# Urukul_FPGA_LVDS.net
KiCad netlist of a schematic drawn in Altium Designer
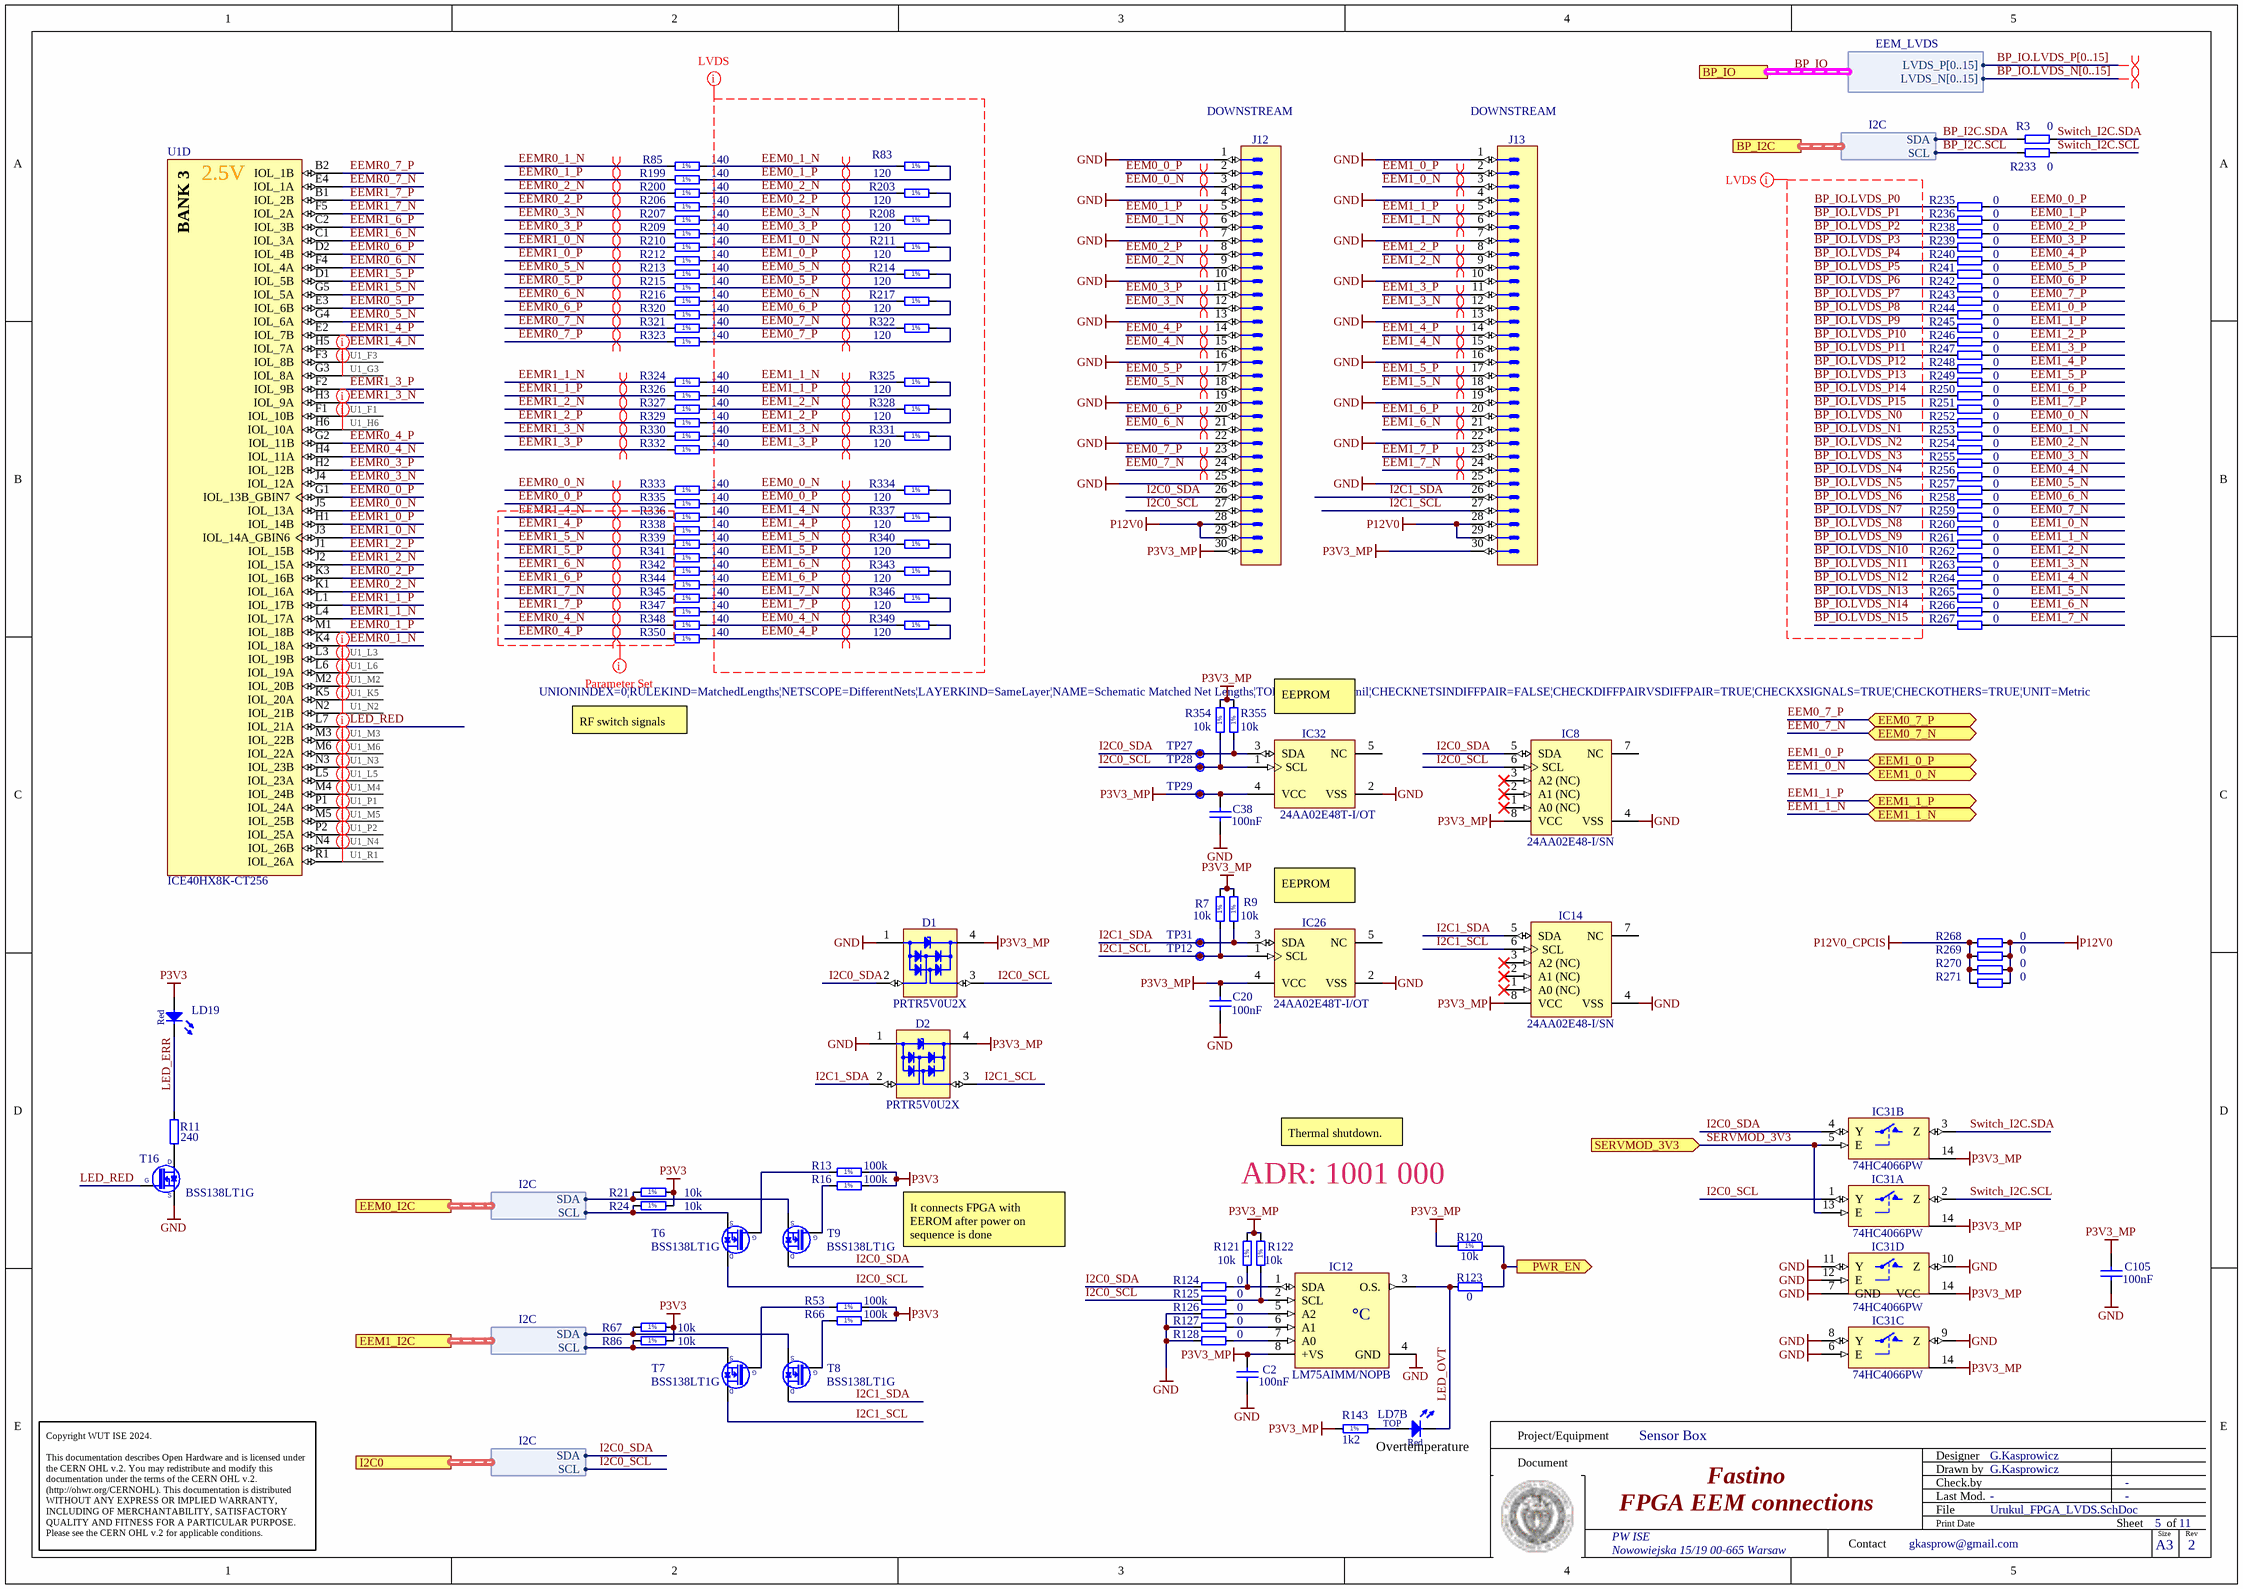
[diagram p0: Urukul_FPGA_LVDS.SchDoc]

(export (version "E")
  (design (tool "Eeschema 10.0.6"))
  (components
    (comp (ref "C2")
      (value "100nF")
      (footprint "CAPC1005X55N")
      (description "Non-polarised capacitor")
      (fields
        (field (name "PART NUMBER") "CC0402_100NF_16V_10%_X5R")
        (field (name "VOLTAGE") "16V")
        (field (name "AUTHOR") "CERN DEM JLC")
      )
      (libsource (lib "Capacitors") (part "Capacitor - non polarized"))
    )
    (comp (ref "C20")
      (value "100nF")
      (footprint "CAPC1005X55N")
      (description "Non-polarised capacitor")
      (fields
        (field (name "PART NUMBER") "CC0402_100NF_16V_10%_X5R")
        (field (name "VOLTAGE") "16V")
        (field (name "AUTHOR") "CERN DEM JLC")
      )
      (libsource (lib "Capacitors") (part "Capacitor - non polarized"))
    )
    (comp (ref "C38")
      (value "100nF")
      (footprint "CAPC1005X55N")
      (description "Non-polarised capacitor")
      (fields
        (field (name "PART NUMBER") "CC0402_100NF_16V_10%_X5R")
        (field (name "VOLTAGE") "16V")
        (field (name "AUTHOR") "CERN DEM JLC")
      )
      (libsource (lib "Capacitors") (part "Capacitor - non polarized"))
    )
    (comp (ref "C105")
      (value "100nF")
      (footprint "CAPC1005X55N")
      (description "Non-polarised capacitor")
      (fields
        (field (name "PART NUMBER") "CC0402_100NF_16V_10%_X5R")
        (field (name "VOLTAGE") "16V")
        (field (name "AUTHOR") "CERN DEM JLC")
      )
      (libsource (lib "Capacitors") (part "Capacitor - non polarized"))
    )
    (comp (ref "D1")
      (value "PRTR5V0U2X")
      (footprint "SOT190P230X110-4N")
      (description "Ultra Low Capacitance Double Rail-to-Rail ESD Protection Diode")
      (fields
        (field (name "VOLTAGE") "5.5V")
        (field (name "MANUFACTURER") "NXP SEMICONDUCTORS")
        (field (name "AUTHOR") "CERN DEM JLC")
      )
      (libsource (lib "ICs And Semiconductors") (part "PRTR5V0U2X"))
    )
    (comp (ref "D2")
      (value "PRTR5V0U2X")
      (footprint "SOT190P230X110-4N")
      (description "Ultra Low Capacitance Double Rail-to-Rail ESD Protection Diode")
      (fields
        (field (name "VOLTAGE") "5.5V")
        (field (name "MANUFACTURER") "NXP SEMICONDUCTORS")
        (field (name "AUTHOR") "CERN DEM JLC")
      )
      (libsource (lib "ICs And Semiconductors") (part "PRTR5V0U2X"))
    )
    (comp (ref "IC8")
      (value "24AA02E48-I/SN")
      (footprint "SOIC127P600X175-8N")
      (description "1.7V-5.5V, 2K I2C™ Serial EEPROMs with EUI-48™ Node Identity")
      (fields (field (name "MANUFACTURER") "MICROCHIP TECHNOLOGY") (field (name "AUTHOR") "CERN DEM MR"))
      (libsource (lib "ICS-logic") (part "MEM_24AA02E48-I/SN"))
    )
    (comp (ref "IC12")
      (value "LM75AIMM/NOPB")
      (footprint "SOP65P490X109-8N")
      (description "Digital Temperature Sensor and Thermal Watchdog with Two-Wire Interface")
      (fields (field (name "MANUFACTURER") "TEXAS INSTRUMENTS") (field (name "AUTHOR") "CERN DEM JLC"))
      (libsource (lib "ICs And Semiconductors") (part "LM75"))
    )
    (comp (ref "IC14")
      (value "24AA02E48-I/SN")
      (footprint "SOIC127P600X175-8N")
      (description "1.7V-5.5V, 2K I2C™ Serial EEPROMs with EUI-48™ Node Identity")
      (fields (field (name "MANUFACTURER") "MICROCHIP TECHNOLOGY") (field (name "AUTHOR") "CERN DEM MR"))
      (libsource (lib "ICS-logic") (part "MEM_24AA02E48-I/SN"))
    )
    (comp (ref "IC26")
      (value "24AA02E48T-I/OT")
      (footprint "SOT95P280X145-5N")
      (description "1.7V-5.5V, 2K I2C Serial EEPROM With EUI-48 Node Identity")
      (fields (field (name "MANUFACTURER") "MICROCHIP TECHNOLOGY") (field (name "AUTHOR") "CERN DEM MR"))
      (libsource (lib "ICs And Semiconductors") (part "24AA02E48T-I/OT"))
    )
    (comp (ref "IC31")
      (value "74HC4066PW")
      (footprint "SOP65P640X110-14N")
      (fields (field (name "MANUFACTURER") "NXP SEMICONDUCTORS") (field (name "AUTHOR") "CERN DEM JLC"))
      (libsource (lib "ICs And Semiconductors") (part "4066"))
    )
    (comp (ref "IC32")
      (value "24AA02E48T-I/OT")
      (footprint "SOT95P280X145-5N")
      (description "1.7V-5.5V, 2K I2C Serial EEPROM With EUI-48 Node Identity")
      (fields (field (name "MANUFACTURER") "MICROCHIP TECHNOLOGY") (field (name "AUTHOR") "CERN DEM MR"))
      (libsource (lib "ICs And Semiconductors") (part "24AA02E48T-I/OT"))
    )
    (comp (ref "J12")
      (value "~")
      (footprint "3M_N2530-6002RB")
      (description "Connector 30 Male")
      (fields
        (field (name "PART NUMBER") "3M_N2530-6002RB")
        (field (name "MANUFACTURER") "3M")
        (field (name "AUTHOR") "CERN DEM JLC")
      )
      (libsource (lib "Connectors") (part "Connector 30 Male"))
    )
    (comp (ref "J13")
      (value "~")
      (footprint "3M_N2530-6002RB")
      (description "Connector 30 Male")
      (fields
        (field (name "PART NUMBER") "3M_N2530-6002RB")
        (field (name "MANUFACTURER") "3M")
        (field (name "AUTHOR") "CERN DEM JLC")
      )
      (libsource (lib "Connectors") (part "Connector 30 Male"))
    )
    (comp (ref "LD7")
      (value "Red/Green")
      (footprint "LED_DIALIGHT_571-0112F")
      (description "2x LED  Botom Green, Top Red")
      (fields
        (field (name "PART NUMBER") "LED_DIALIGHT_571-0112F")
        (field (name "MANUFACTURER") "DIALIGHT")
        (field (name "AUTHOR") "CERN DEM JLC")
      )
      (libsource (lib "ICs And Semiconductors") (part "LED x2 G-1C2A-BOT_R-3C4A-TOP"))
    )
    (comp (ref "LD19")
      (value "Red")
      (footprint "LED_AVAGO_HSMC-C120")
      (description "LED Red 1C 2A")
      (fields
        (field (name "PART NUMBER") "LED_AVAGO_HSMC-C120")
        (field (name "MANUFACTURER") "AVAGO TECHNOLOGIES")
        (field (name "AUTHOR") "CERN DEM JMW")
      )
      (libsource (lib "ICs And Semiconductors") (part "LED Red 1C 2A"))
    )
    (comp (ref "R3")
      (value "0")
      (footprint "RESC1005X40N")
      (description "Resistor")
      (fields
        (field (name "PART NUMBER") "R0402_0R_JUMPER")
        (field (name "MANUFACTURER") "GENERIC")
        (field (name "AUTHOR") "CERN DEM JLC")
      )
      (libsource (lib "Resistors") (part "Resistor"))
    )
    (comp (ref "R7")
      (value "10k")
      (footprint "RESC1005X40N")
      (description "Resistor - 1%")
      (fields
        (field (name "PART NUMBER") "R0402_10K_1%_0.0625W_100PPM")
        (field (name "POWER") "0.0625W")
        (field (name "AUTHOR") "CERN DEM JLC")
      )
      (libsource (lib "Resistors") (part "Resistor - 1%"))
    )
    (comp (ref "R9")
      (value "10k")
      (footprint "RESC1005X40N")
      (description "Resistor - 1%")
      (fields
        (field (name "PART NUMBER") "R0402_10K_1%_0.0625W_100PPM")
        (field (name "POWER") "0.0625W")
        (field (name "AUTHOR") "CERN DEM JLC")
      )
      (libsource (lib "Resistors") (part "Resistor - 1%"))
    )
    (comp (ref "R11")
      (value "240")
      (footprint "RESC1005X40N")
      (description "Resistor - 1%")
      (fields
        (field (name "PART NUMBER") "R0402_240R_1%_0.0625W_100PPM")
        (field (name "POWER") "0.0625W")
        (field (name "AUTHOR") "CERN DEM JLC")
      )
      (libsource (lib "Resistors") (part "Resistor - 1%"))
    )
    (comp (ref "R13")
      (value "100k")
      (footprint "RESC1005X40N")
      (description "Resistor - 1%")
      (fields
        (field (name "PART NUMBER") "R0402_100K_1%_0.0625W_100PPM")
        (field (name "POWER") "0.0625W")
        (field (name "AUTHOR") "CERN DEM JLC")
      )
      (libsource (lib "Resistors") (part "Resistor - 1%"))
    )
    (comp (ref "R16")
      (value "100k")
      (footprint "RESC1005X40N")
      (description "Resistor - 1%")
      (fields
        (field (name "PART NUMBER") "R0402_100K_1%_0.0625W_100PPM")
        (field (name "POWER") "0.0625W")
        (field (name "AUTHOR") "CERN DEM JLC")
      )
      (libsource (lib "Resistors") (part "Resistor - 1%"))
    )
    (comp (ref "R21")
      (value "10k")
      (footprint "RESC1005X40N")
      (description "Resistor - 1%")
      (fields
        (field (name "PART NUMBER") "R0402_10K_1%_0.0625W_100PPM")
        (field (name "POWER") "0.0625W")
        (field (name "AUTHOR") "CERN DEM JLC")
      )
      (libsource (lib "Resistors") (part "Resistor - 1%"))
    )
    (comp (ref "R24")
      (value "10k")
      (footprint "RESC1005X40N")
      (description "Resistor - 1%")
      (fields
        (field (name "PART NUMBER") "R0402_10K_1%_0.0625W_100PPM")
        (field (name "POWER") "0.0625W")
        (field (name "AUTHOR") "CERN DEM JLC")
      )
      (libsource (lib "Resistors") (part "Resistor - 1%"))
    )
    (comp (ref "R53")
      (value "100k")
      (footprint "RESC1005X40N")
      (description "Resistor - 1%")
      (fields
        (field (name "PART NUMBER") "R0402_100K_1%_0.0625W_100PPM")
        (field (name "POWER") "0.0625W")
        (field (name "AUTHOR") "CERN DEM JLC")
      )
      (libsource (lib "Resistors") (part "Resistor - 1%"))
    )
    (comp (ref "R66")
      (value "100k")
      (footprint "RESC1005X40N")
      (description "Resistor - 1%")
      (fields
        (field (name "PART NUMBER") "R0402_100K_1%_0.0625W_100PPM")
        (field (name "POWER") "0.0625W")
        (field (name "AUTHOR") "CERN DEM JLC")
      )
      (libsource (lib "Resistors") (part "Resistor - 1%"))
    )
    (comp (ref "R67")
      (value "10k")
      (footprint "RESC1005X40N")
      (description "Resistor - 1%")
      (fields
        (field (name "PART NUMBER") "R0402_10K_1%_0.0625W_100PPM")
        (field (name "POWER") "0.0625W")
        (field (name "AUTHOR") "CERN DEM JLC")
      )
      (libsource (lib "Resistors") (part "Resistor - 1%"))
    )
    (comp (ref "R83")
      (value "120")
      (footprint "RESC1005X40N")
      (description "Resistor - 1%")
      (fields
        (field (name "PART NUMBER") "R0402_120R_1%_0.0625W_100PPM")
        (field (name "POWER") "0.0625W")
        (field (name "AUTHOR") "CERN DEM JLC")
      )
      (libsource (lib "Resistors") (part "Resistor - 1%"))
    )
    (comp (ref "R85")
      (value "140")
      (footprint "RESC0603X28N")
      (description "Resistor - 1%")
      (fields
        (field (name "PART NUMBER") "R0201_140R_1%_0.05W_200PPM")
        (field (name "POWER") "0.05W")
        (field (name "AUTHOR") "CERN DEM MR")
      )
      (libsource (lib "Resistors") (part "Resistor - 1%"))
    )
    (comp (ref "R86")
      (value "10k")
      (footprint "RESC1005X40N")
      (description "Resistor - 1%")
      (fields
        (field (name "PART NUMBER") "R0402_10K_1%_0.0625W_100PPM")
        (field (name "POWER") "0.0625W")
        (field (name "AUTHOR") "CERN DEM JLC")
      )
      (libsource (lib "Resistors") (part "Resistor - 1%"))
    )
    (comp (ref "R120")
      (value "10k")
      (footprint "RESC1005X40N")
      (description "Resistor - 1%")
      (fields
        (field (name "PART NUMBER") "R0402_10K_1%_0.0625W_100PPM")
        (field (name "POWER") "0.0625W")
        (field (name "AUTHOR") "CERN DEM JLC")
      )
      (libsource (lib "Resistors") (part "Resistor - 1%"))
    )
    (comp (ref "R121")
      (value "10k")
      (footprint "RESC1005X40N")
      (description "Resistor - 1%")
      (fields
        (field (name "PART NUMBER") "R0402_10K_1%_0.0625W_100PPM")
        (field (name "POWER") "0.0625W")
        (field (name "AUTHOR") "CERN DEM JLC")
      )
      (libsource (lib "Resistors") (part "Resistor - 1%"))
    )
    (comp (ref "R122")
      (value "10k")
      (footprint "RESC1005X40N")
      (description "Resistor - 1%")
      (fields
        (field (name "PART NUMBER") "R0402_10K_1%_0.0625W_100PPM")
        (field (name "POWER") "0.0625W")
        (field (name "AUTHOR") "CERN DEM JLC")
      )
      (libsource (lib "Resistors") (part "Resistor - 1%"))
    )
    (comp (ref "R123")
      (value "0")
      (footprint "RESC1005X40N")
      (description "Resistor")
      (fields
        (field (name "PART NUMBER") "R0402_0R_JUMPER")
        (field (name "MANUFACTURER") "GENERIC")
        (field (name "AUTHOR") "CERN DEM JLC")
      )
      (libsource (lib "Resistors") (part "Resistor"))
    )
    (comp (ref "R124")
      (value "0")
      (footprint "RESC1005X40N")
      (description "Resistor")
      (fields
        (field (name "PART NUMBER") "R0402_0R_JUMPER")
        (field (name "MANUFACTURER") "GENERIC")
        (field (name "AUTHOR") "CERN DEM JLC")
      )
      (libsource (lib "Resistors") (part "Resistor"))
    )
    (comp (ref "R125")
      (value "0")
      (footprint "RESC1005X40N")
      (description "Resistor")
      (fields
        (field (name "PART NUMBER") "R0402_0R_JUMPER")
        (field (name "MANUFACTURER") "GENERIC")
        (field (name "AUTHOR") "CERN DEM JLC")
      )
      (libsource (lib "Resistors") (part "Resistor"))
    )
    (comp (ref "R126")
      (value "0")
      (footprint "RESC1005X40N")
      (description "Resistor")
      (fields
        (field (name "PART NUMBER") "R0402_0R_JUMPER")
        (field (name "MANUFACTURER") "GENERIC")
        (field (name "AUTHOR") "CERN DEM JLC")
      )
      (libsource (lib "Resistors") (part "Resistor"))
    )
    (comp (ref "R127")
      (value "0")
      (footprint "RESC1005X40N")
      (description "Resistor")
      (fields
        (field (name "PART NUMBER") "R0402_0R_JUMPER")
        (field (name "MANUFACTURER") "GENERIC")
        (field (name "AUTHOR") "CERN DEM JLC")
      )
      (libsource (lib "Resistors") (part "Resistor"))
    )
    (comp (ref "R128")
      (value "0")
      (footprint "RESC1005X40N")
      (description "Resistor")
      (fields
        (field (name "PART NUMBER") "R0402_0R_JUMPER")
        (field (name "MANUFACTURER") "GENERIC")
        (field (name "AUTHOR") "CERN DEM JLC")
      )
      (libsource (lib "Resistors") (part "Resistor"))
    )
    (comp (ref "R143")
      (value "1k2")
      (footprint "RESC1608X55N")
      (description "Resistor - 1%")
      (fields
        (field (name "PART NUMBER") "R0603_1K2_1%_0.1W_100PPM")
        (field (name "POWER") "0.1W")
        (field (name "AUTHOR") "CERN DEM JLC")
      )
      (libsource (lib "Resistors") (part "Resistor - 1%"))
    )
    (comp (ref "R199")
      (value "140")
      (footprint "RESC0603X28N")
      (description "Resistor - 1%")
      (fields
        (field (name "PART NUMBER") "R0201_140R_1%_0.05W_200PPM")
        (field (name "POWER") "0.05W")
        (field (name "AUTHOR") "CERN DEM MR")
      )
      (libsource (lib "Resistors") (part "Resistor - 1%"))
    )
    (comp (ref "R200")
      (value "140")
      (footprint "RESC0603X28N")
      (description "Resistor - 1%")
      (fields
        (field (name "PART NUMBER") "R0201_140R_1%_0.05W_200PPM")
        (field (name "POWER") "0.05W")
        (field (name "AUTHOR") "CERN DEM MR")
      )
      (libsource (lib "Resistors") (part "Resistor - 1%"))
    )
    (comp (ref "R203")
      (value "120")
      (footprint "RESC1005X40N")
      (description "Resistor - 1%")
      (fields
        (field (name "PART NUMBER") "R0402_120R_1%_0.0625W_100PPM")
        (field (name "POWER") "0.0625W")
        (field (name "AUTHOR") "CERN DEM JLC")
      )
      (libsource (lib "Resistors") (part "Resistor - 1%"))
    )
    (comp (ref "R206")
      (value "140")
      (footprint "RESC0603X28N")
      (description "Resistor - 1%")
      (fields
        (field (name "PART NUMBER") "R0201_140R_1%_0.05W_200PPM")
        (field (name "POWER") "0.05W")
        (field (name "AUTHOR") "CERN DEM MR")
      )
      (libsource (lib "Resistors") (part "Resistor - 1%"))
    )
    (comp (ref "R207")
      (value "140")
      (footprint "RESC0603X28N")
      (description "Resistor - 1%")
      (fields
        (field (name "PART NUMBER") "R0201_140R_1%_0.05W_200PPM")
        (field (name "POWER") "0.05W")
        (field (name "AUTHOR") "CERN DEM MR")
      )
      (libsource (lib "Resistors") (part "Resistor - 1%"))
    )
    (comp (ref "R208")
      (value "120")
      (footprint "RESC1005X40N")
      (description "Resistor - 1%")
      (fields
        (field (name "PART NUMBER") "R0402_120R_1%_0.0625W_100PPM")
        (field (name "POWER") "0.0625W")
        (field (name "AUTHOR") "CERN DEM JLC")
      )
      (libsource (lib "Resistors") (part "Resistor - 1%"))
    )
    (comp (ref "R209")
      (value "140")
      (footprint "RESC0603X28N")
      (description "Resistor - 1%")
      (fields
        (field (name "PART NUMBER") "R0201_140R_1%_0.05W_200PPM")
        (field (name "POWER") "0.05W")
        (field (name "AUTHOR") "CERN DEM MR")
      )
      (libsource (lib "Resistors") (part "Resistor - 1%"))
    )
    (comp (ref "R210")
      (value "140")
      (footprint "RESC0603X28N")
      (description "Resistor - 1%")
      (fields
        (field (name "PART NUMBER") "R0201_140R_1%_0.05W_200PPM")
        (field (name "POWER") "0.05W")
        (field (name "AUTHOR") "CERN DEM MR")
      )
      (libsource (lib "Resistors") (part "Resistor - 1%"))
    )
    (comp (ref "R211")
      (value "120")
      (footprint "RESC1005X40N")
      (description "Resistor - 1%")
      (fields
        (field (name "PART NUMBER") "R0402_120R_1%_0.0625W_100PPM")
        (field (name "POWER") "0.0625W")
        (field (name "AUTHOR") "CERN DEM JLC")
      )
      (libsource (lib "Resistors") (part "Resistor - 1%"))
    )
    (comp (ref "R212")
      (value "140")
      (footprint "RESC0603X28N")
      (description "Resistor - 1%")
      (fields
        (field (name "PART NUMBER") "R0201_140R_1%_0.05W_200PPM")
        (field (name "POWER") "0.05W")
        (field (name "AUTHOR") "CERN DEM MR")
      )
      (libsource (lib "Resistors") (part "Resistor - 1%"))
    )
    (comp (ref "R213")
      (value "140")
      (footprint "RESC0603X28N")
      (description "Resistor - 1%")
      (fields
        (field (name "PART NUMBER") "R0201_140R_1%_0.05W_200PPM")
        (field (name "POWER") "0.05W")
        (field (name "AUTHOR") "CERN DEM MR")
      )
      (libsource (lib "Resistors") (part "Resistor - 1%"))
    )
    (comp (ref "R214")
      (value "120")
      (footprint "RESC1005X40N")
      (description "Resistor - 1%")
      (fields
        (field (name "PART NUMBER") "R0402_120R_1%_0.0625W_100PPM")
        (field (name "POWER") "0.0625W")
        (field (name "AUTHOR") "CERN DEM JLC")
      )
      (libsource (lib "Resistors") (part "Resistor - 1%"))
    )
    (comp (ref "R215")
      (value "140")
      (footprint "RESC0603X28N")
      (description "Resistor - 1%")
      (fields
        (field (name "PART NUMBER") "R0201_140R_1%_0.05W_200PPM")
        (field (name "POWER") "0.05W")
        (field (name "AUTHOR") "CERN DEM MR")
      )
      (libsource (lib "Resistors") (part "Resistor - 1%"))
    )
    (comp (ref "R216")
      (value "140")
      (footprint "RESC0603X28N")
      (description "Resistor - 1%")
      (fields
        (field (name "PART NUMBER") "R0201_140R_1%_0.05W_200PPM")
        (field (name "POWER") "0.05W")
        (field (name "AUTHOR") "CERN DEM MR")
      )
      (libsource (lib "Resistors") (part "Resistor - 1%"))
    )
    (comp (ref "R217")
      (value "120")
      (footprint "RESC1005X40N")
      (description "Resistor - 1%")
      (fields
        (field (name "PART NUMBER") "R0402_120R_1%_0.0625W_100PPM")
        (field (name "POWER") "0.0625W")
        (field (name "AUTHOR") "CERN DEM JLC")
      )
      (libsource (lib "Resistors") (part "Resistor - 1%"))
    )
    (comp (ref "R233")
      (value "0")
      (footprint "RESC1005X40N")
      (description "Resistor")
      (fields
        (field (name "PART NUMBER") "R0402_0R_JUMPER")
        (field (name "MANUFACTURER") "GENERIC")
        (field (name "AUTHOR") "CERN DEM JLC")
      )
      (libsource (lib "Resistors") (part "Resistor"))
    )
    (comp (ref "R235")
      (value "0")
      (footprint "RESC1005X40N")
      (description "Resistor")
      (fields
        (field (name "PART NUMBER") "R0402_0R_JUMPER")
        (field (name "MANUFACTURER") "GENERIC")
        (field (name "AUTHOR") "CERN DEM JLC")
      )
      (libsource (lib "Resistors") (part "Resistor"))
    )
    (comp (ref "R236")
      (value "0")
      (footprint "RESC1005X40N")
      (description "Resistor")
      (fields
        (field (name "PART NUMBER") "R0402_0R_JUMPER")
        (field (name "MANUFACTURER") "GENERIC")
        (field (name "AUTHOR") "CERN DEM JLC")
      )
      (libsource (lib "Resistors") (part "Resistor"))
    )
    (comp (ref "R238")
      (value "0")
      (footprint "RESC1005X40N")
      (description "Resistor")
      (fields
        (field (name "PART NUMBER") "R0402_0R_JUMPER")
        (field (name "MANUFACTURER") "GENERIC")
        (field (name "AUTHOR") "CERN DEM JLC")
      )
      (libsource (lib "Resistors") (part "Resistor"))
    )
    (comp (ref "R239")
      (value "0")
      (footprint "RESC1005X40N")
      (description "Resistor")
      (fields
        (field (name "PART NUMBER") "R0402_0R_JUMPER")
        (field (name "MANUFACTURER") "GENERIC")
        (field (name "AUTHOR") "CERN DEM JLC")
      )
      (libsource (lib "Resistors") (part "Resistor"))
    )
    (comp (ref "R240")
      (value "0")
      (footprint "RESC1005X40N")
      (description "Resistor")
      (fields
        (field (name "PART NUMBER") "R0402_0R_JUMPER")
        (field (name "MANUFACTURER") "GENERIC")
        (field (name "AUTHOR") "CERN DEM JLC")
      )
      (libsource (lib "Resistors") (part "Resistor"))
    )
    (comp (ref "R241")
      (value "0")
      (footprint "RESC1005X40N")
      (description "Resistor")
      (fields
        (field (name "PART NUMBER") "R0402_0R_JUMPER")
        (field (name "MANUFACTURER") "GENERIC")
        (field (name "AUTHOR") "CERN DEM JLC")
      )
      (libsource (lib "Resistors") (part "Resistor"))
    )
    (comp (ref "R242")
      (value "0")
      (footprint "RESC1005X40N")
      (description "Resistor")
      (fields
        (field (name "PART NUMBER") "R0402_0R_JUMPER")
        (field (name "MANUFACTURER") "GENERIC")
        (field (name "AUTHOR") "CERN DEM JLC")
      )
      (libsource (lib "Resistors") (part "Resistor"))
    )
    (comp (ref "R243")
      (value "0")
      (footprint "RESC1005X40N")
      (description "Resistor")
      (fields
        (field (name "PART NUMBER") "R0402_0R_JUMPER")
        (field (name "MANUFACTURER") "GENERIC")
        (field (name "AUTHOR") "CERN DEM JLC")
      )
      (libsource (lib "Resistors") (part "Resistor"))
    )
    (comp (ref "R244")
      (value "0")
      (footprint "RESC1005X40N")
      (description "Resistor")
      (fields
        (field (name "PART NUMBER") "R0402_0R_JUMPER")
        (field (name "MANUFACTURER") "GENERIC")
        (field (name "AUTHOR") "CERN DEM JLC")
      )
      (libsource (lib "Resistors") (part "Resistor"))
    )
    (comp (ref "R245")
      (value "0")
      (footprint "RESC1005X40N")
      (description "Resistor")
      (fields
        (field (name "PART NUMBER") "R0402_0R_JUMPER")
        (field (name "MANUFACTURER") "GENERIC")
        (field (name "AUTHOR") "CERN DEM JLC")
      )
      (libsource (lib "Resistors") (part "Resistor"))
    )
    (comp (ref "R246")
      (value "0")
      (footprint "RESC1005X40N")
      (description "Resistor")
      (fields
        (field (name "PART NUMBER") "R0402_0R_JUMPER")
        (field (name "MANUFACTURER") "GENERIC")
        (field (name "AUTHOR") "CERN DEM JLC")
      )
      (libsource (lib "Resistors") (part "Resistor"))
    )
    (comp (ref "R247")
      (value "0")
      (footprint "RESC1005X40N")
      (description "Resistor")
      (fields
        (field (name "PART NUMBER") "R0402_0R_JUMPER")
        (field (name "MANUFACTURER") "GENERIC")
        (field (name "AUTHOR") "CERN DEM JLC")
      )
      (libsource (lib "Resistors") (part "Resistor"))
    )
    (comp (ref "R248")
      (value "0")
      (footprint "RESC1005X40N")
      (description "Resistor")
      (fields
        (field (name "PART NUMBER") "R0402_0R_JUMPER")
        (field (name "MANUFACTURER") "GENERIC")
        (field (name "AUTHOR") "CERN DEM JLC")
      )
      (libsource (lib "Resistors") (part "Resistor"))
    )
    (comp (ref "R249")
      (value "0")
      (footprint "RESC1005X40N")
      (description "Resistor")
      (fields
        (field (name "PART NUMBER") "R0402_0R_JUMPER")
        (field (name "MANUFACTURER") "GENERIC")
        (field (name "AUTHOR") "CERN DEM JLC")
      )
      (libsource (lib "Resistors") (part "Resistor"))
    )
    (comp (ref "R250")
      (value "0")
      (footprint "RESC1005X40N")
      (description "Resistor")
      (fields
        (field (name "PART NUMBER") "R0402_0R_JUMPER")
        (field (name "MANUFACTURER") "GENERIC")
        (field (name "AUTHOR") "CERN DEM JLC")
      )
      (libsource (lib "Resistors") (part "Resistor"))
    )
    (comp (ref "R251")
      (value "0")
      (footprint "RESC1005X40N")
      (description "Resistor")
      (fields
        (field (name "PART NUMBER") "R0402_0R_JUMPER")
        (field (name "MANUFACTURER") "GENERIC")
        (field (name "AUTHOR") "CERN DEM JLC")
      )
      (libsource (lib "Resistors") (part "Resistor"))
    )
    (comp (ref "R252")
      (value "0")
      (footprint "RESC1005X40N")
      (description "Resistor")
      (fields
        (field (name "PART NUMBER") "R0402_0R_JUMPER")
        (field (name "MANUFACTURER") "GENERIC")
        (field (name "AUTHOR") "CERN DEM JLC")
      )
      (libsource (lib "Resistors") (part "Resistor"))
    )
    (comp (ref "R253")
      (value "0")
      (footprint "RESC1005X40N")
      (description "Resistor")
      (fields
        (field (name "PART NUMBER") "R0402_0R_JUMPER")
        (field (name "MANUFACTURER") "GENERIC")
        (field (name "AUTHOR") "CERN DEM JLC")
      )
      (libsource (lib "Resistors") (part "Resistor"))
    )
    (comp (ref "R254")
      (value "0")
      (footprint "RESC1005X40N")
      (description "Resistor")
      (fields
        (field (name "PART NUMBER") "R0402_0R_JUMPER")
        (field (name "MANUFACTURER") "GENERIC")
        (field (name "AUTHOR") "CERN DEM JLC")
      )
      (libsource (lib "Resistors") (part "Resistor"))
    )
    (comp (ref "R255")
      (value "0")
      (footprint "RESC1005X40N")
      (description "Resistor")
      (fields
        (field (name "PART NUMBER") "R0402_0R_JUMPER")
        (field (name "MANUFACTURER") "GENERIC")
        (field (name "AUTHOR") "CERN DEM JLC")
      )
      (libsource (lib "Resistors") (part "Resistor"))
    )
    (comp (ref "R256")
      (value "0")
      (footprint "RESC1005X40N")
      (description "Resistor")
      (fields
        (field (name "PART NUMBER") "R0402_0R_JUMPER")
        (field (name "MANUFACTURER") "GENERIC")
        (field (name "AUTHOR") "CERN DEM JLC")
      )
      (libsource (lib "Resistors") (part "Resistor"))
    )
    (comp (ref "R257")
      (value "0")
      (footprint "RESC1005X40N")
      (description "Resistor")
      (fields
        (field (name "PART NUMBER") "R0402_0R_JUMPER")
        (field (name "MANUFACTURER") "GENERIC")
        (field (name "AUTHOR") "CERN DEM JLC")
      )
      (libsource (lib "Resistors") (part "Resistor"))
    )
    (comp (ref "R258")
      (value "0")
      (footprint "RESC1005X40N")
      (description "Resistor")
      (fields
        (field (name "PART NUMBER") "R0402_0R_JUMPER")
        (field (name "MANUFACTURER") "GENERIC")
        (field (name "AUTHOR") "CERN DEM JLC")
      )
      (libsource (lib "Resistors") (part "Resistor"))
    )
    (comp (ref "R259")
      (value "0")
      (footprint "RESC1005X40N")
      (description "Resistor")
      (fields
        (field (name "PART NUMBER") "R0402_0R_JUMPER")
        (field (name "MANUFACTURER") "GENERIC")
        (field (name "AUTHOR") "CERN DEM JLC")
      )
      (libsource (lib "Resistors") (part "Resistor"))
    )
    (comp (ref "R260")
      (value "0")
      (footprint "RESC1005X40N")
      (description "Resistor")
      (fields
        (field (name "PART NUMBER") "R0402_0R_JUMPER")
        (field (name "MANUFACTURER") "GENERIC")
        (field (name "AUTHOR") "CERN DEM JLC")
      )
      (libsource (lib "Resistors") (part "Resistor"))
    )
    (comp (ref "R261")
      (value "0")
      (footprint "RESC1005X40N")
      (description "Resistor")
      (fields
        (field (name "PART NUMBER") "R0402_0R_JUMPER")
        (field (name "MANUFACTURER") "GENERIC")
        (field (name "AUTHOR") "CERN DEM JLC")
      )
      (libsource (lib "Resistors") (part "Resistor"))
    )
    (comp (ref "R262")
      (value "0")
      (footprint "RESC1005X40N")
      (description "Resistor")
      (fields
        (field (name "PART NUMBER") "R0402_0R_JUMPER")
        (field (name "MANUFACTURER") "GENERIC")
        (field (name "AUTHOR") "CERN DEM JLC")
      )
      (libsource (lib "Resistors") (part "Resistor"))
    )
    (comp (ref "R263")
      (value "0")
      (footprint "RESC1005X40N")
      (description "Resistor")
      (fields
        (field (name "PART NUMBER") "R0402_0R_JUMPER")
        (field (name "MANUFACTURER") "GENERIC")
        (field (name "AUTHOR") "CERN DEM JLC")
      )
      (libsource (lib "Resistors") (part "Resistor"))
    )
    (comp (ref "R264")
      (value "0")
      (footprint "RESC1005X40N")
      (description "Resistor")
      (fields
        (field (name "PART NUMBER") "R0402_0R_JUMPER")
        (field (name "MANUFACTURER") "GENERIC")
        (field (name "AUTHOR") "CERN DEM JLC")
      )
      (libsource (lib "Resistors") (part "Resistor"))
    )
    (comp (ref "R265")
      (value "0")
      (footprint "RESC1005X40N")
      (description "Resistor")
      (fields
        (field (name "PART NUMBER") "R0402_0R_JUMPER")
        (field (name "MANUFACTURER") "GENERIC")
        (field (name "AUTHOR") "CERN DEM JLC")
      )
      (libsource (lib "Resistors") (part "Resistor"))
    )
    (comp (ref "R266")
      (value "0")
      (footprint "RESC1005X40N")
      (description "Resistor")
      (fields
        (field (name "PART NUMBER") "R0402_0R_JUMPER")
        (field (name "MANUFACTURER") "GENERIC")
        (field (name "AUTHOR") "CERN DEM JLC")
      )
      (libsource (lib "Resistors") (part "Resistor"))
    )
    (comp (ref "R267")
      (value "0")
      (footprint "RESC1005X40N")
      (description "Resistor")
      (fields
        (field (name "PART NUMBER") "R0402_0R_JUMPER")
        (field (name "MANUFACTURER") "GENERIC")
        (field (name "AUTHOR") "CERN DEM JLC")
      )
      (libsource (lib "Resistors") (part "Resistor"))
    )
    (comp (ref "R268")
      (value "0")
      (footprint "RESC1005X40N")
      (description "Resistor")
      (fields
        (field (name "PART NUMBER") "R0402_0R_JUMPER")
        (field (name "MANUFACTURER") "GENERIC")
        (field (name "AUTHOR") "CERN DEM JLC")
      )
      (libsource (lib "Resistors") (part "Resistor"))
    )
    (comp (ref "R269")
      (value "0")
      (footprint "RESC1005X40N")
      (description "Resistor")
      (fields
        (field (name "PART NUMBER") "R0402_0R_JUMPER")
        (field (name "MANUFACTURER") "GENERIC")
        (field (name "AUTHOR") "CERN DEM JLC")
      )
      (libsource (lib "Resistors") (part "Resistor"))
    )
    (comp (ref "R270")
      (value "0")
      (footprint "RESC1005X40N")
      (description "Resistor")
      (fields
        (field (name "PART NUMBER") "R0402_0R_JUMPER")
        (field (name "MANUFACTURER") "GENERIC")
        (field (name "AUTHOR") "CERN DEM JLC")
      )
      (libsource (lib "Resistors") (part "Resistor"))
    )
    (comp (ref "R271")
      (value "0")
      (footprint "RESC1005X40N")
      (description "Resistor")
      (fields
        (field (name "PART NUMBER") "R0402_0R_JUMPER")
        (field (name "MANUFACTURER") "GENERIC")
        (field (name "AUTHOR") "CERN DEM JLC")
      )
      (libsource (lib "Resistors") (part "Resistor"))
    )
    (comp (ref "R320")
      (value "140")
      (footprint "RESC0603X28N")
      (description "Resistor - 1%")
      (fields
        (field (name "PART NUMBER") "R0201_140R_1%_0.05W_200PPM")
        (field (name "POWER") "0.05W")
        (field (name "AUTHOR") "CERN DEM MR")
      )
      (libsource (lib "Resistors") (part "Resistor - 1%"))
    )
    (comp (ref "R321")
      (value "140")
      (footprint "RESC0603X28N")
      (description "Resistor - 1%")
      (fields
        (field (name "PART NUMBER") "R0201_140R_1%_0.05W_200PPM")
        (field (name "POWER") "0.05W")
        (field (name "AUTHOR") "CERN DEM MR")
      )
      (libsource (lib "Resistors") (part "Resistor - 1%"))
    )
    (comp (ref "R322")
      (value "120")
      (footprint "RESC1005X40N")
      (description "Resistor - 1%")
      (fields
        (field (name "PART NUMBER") "R0402_120R_1%_0.0625W_100PPM")
        (field (name "POWER") "0.0625W")
        (field (name "AUTHOR") "CERN DEM JLC")
      )
      (libsource (lib "Resistors") (part "Resistor - 1%"))
    )
    (comp (ref "R323")
      (value "140")
      (footprint "RESC0603X28N")
      (description "Resistor - 1%")
      (fields
        (field (name "PART NUMBER") "R0201_140R_1%_0.05W_200PPM")
        (field (name "POWER") "0.05W")
        (field (name "AUTHOR") "CERN DEM MR")
      )
      (libsource (lib "Resistors") (part "Resistor - 1%"))
    )
    (comp (ref "R324")
      (value "140")
      (footprint "RESC0603X28N")
      (description "Resistor - 1%")
      (fields
        (field (name "PART NUMBER") "R0201_140R_1%_0.05W_200PPM")
        (field (name "POWER") "0.05W")
        (field (name "AUTHOR") "CERN DEM MR")
      )
      (libsource (lib "Resistors") (part "Resistor - 1%"))
    )
    (comp (ref "R325")
      (value "120")
      (footprint "RESC1005X40N")
      (description "Resistor - 1%")
      (fields
        (field (name "PART NUMBER") "R0402_120R_1%_0.0625W_100PPM")
        (field (name "POWER") "0.0625W")
        (field (name "AUTHOR") "CERN DEM JLC")
      )
      (libsource (lib "Resistors") (part "Resistor - 1%"))
    )
    (comp (ref "R326")
      (value "140")
      (footprint "RESC0603X28N")
      (description "Resistor - 1%")
      (fields
        (field (name "PART NUMBER") "R0201_140R_1%_0.05W_200PPM")
        (field (name "POWER") "0.05W")
        (field (name "AUTHOR") "CERN DEM MR")
      )
      (libsource (lib "Resistors") (part "Resistor - 1%"))
    )
    (comp (ref "R327")
      (value "140")
      (footprint "RESC0603X28N")
      (description "Resistor - 1%")
      (fields
        (field (name "PART NUMBER") "R0201_140R_1%_0.05W_200PPM")
        (field (name "POWER") "0.05W")
        (field (name "AUTHOR") "CERN DEM MR")
      )
      (libsource (lib "Resistors") (part "Resistor - 1%"))
    )
    (comp (ref "R328")
      (value "120")
      (footprint "RESC1005X40N")
      (description "Resistor - 1%")
      (fields
        (field (name "PART NUMBER") "R0402_120R_1%_0.0625W_100PPM")
        (field (name "POWER") "0.0625W")
        (field (name "AUTHOR") "CERN DEM JLC")
      )
      (libsource (lib "Resistors") (part "Resistor - 1%"))
    )
    (comp (ref "R329")
      (value "140")
      (footprint "RESC0603X28N")
      (description "Resistor - 1%")
      (fields
        (field (name "PART NUMBER") "R0201_140R_1%_0.05W_200PPM")
        (field (name "POWER") "0.05W")
        (field (name "AUTHOR") "CERN DEM MR")
      )
      (libsource (lib "Resistors") (part "Resistor - 1%"))
    )
    (comp (ref "R330")
      (value "140")
      (footprint "RESC0603X28N")
      (description "Resistor - 1%")
      (fields
        (field (name "PART NUMBER") "R0201_140R_1%_0.05W_200PPM")
        (field (name "POWER") "0.05W")
        (field (name "AUTHOR") "CERN DEM MR")
      )
      (libsource (lib "Resistors") (part "Resistor - 1%"))
    )
    (comp (ref "R331")
      (value "120")
      (footprint "RESC1005X40N")
      (description "Resistor - 1%")
      (fields
        (field (name "PART NUMBER") "R0402_120R_1%_0.0625W_100PPM")
        (field (name "POWER") "0.0625W")
        (field (name "AUTHOR") "CERN DEM JLC")
      )
      (libsource (lib "Resistors") (part "Resistor - 1%"))
    )
    (comp (ref "R332")
      (value "140")
      (footprint "RESC0603X28N")
      (description "Resistor - 1%")
      (fields
        (field (name "PART NUMBER") "R0201_140R_1%_0.05W_200PPM")
        (field (name "POWER") "0.05W")
        (field (name "AUTHOR") "CERN DEM MR")
      )
      (libsource (lib "Resistors") (part "Resistor - 1%"))
    )
    (comp (ref "R333")
      (value "140")
      (footprint "RESC0603X28N")
      (description "Resistor - 1%")
      (fields
        (field (name "PART NUMBER") "R0201_140R_1%_0.05W_200PPM")
        (field (name "POWER") "0.05W")
        (field (name "AUTHOR") "CERN DEM MR")
      )
      (libsource (lib "Resistors") (part "Resistor - 1%"))
    )
    (comp (ref "R334")
      (value "120")
      (footprint "RESC1005X40N")
      (description "Resistor - 1%")
      (fields
        (field (name "PART NUMBER") "R0402_120R_1%_0.0625W_100PPM")
        (field (name "POWER") "0.0625W")
        (field (name "AUTHOR") "CERN DEM JLC")
      )
      (libsource (lib "Resistors") (part "Resistor - 1%"))
    )
    (comp (ref "R335")
      (value "140")
      (footprint "RESC0603X28N")
      (description "Resistor - 1%")
      (fields
        (field (name "PART NUMBER") "R0201_140R_1%_0.05W_200PPM")
        (field (name "POWER") "0.05W")
        (field (name "AUTHOR") "CERN DEM MR")
      )
      (libsource (lib "Resistors") (part "Resistor - 1%"))
    )
    (comp (ref "R336")
      (value "140")
      (footprint "RESC0603X28N")
      (description "Resistor - 1%")
      (fields
        (field (name "PART NUMBER") "R0201_140R_1%_0.05W_200PPM")
        (field (name "POWER") "0.05W")
        (field (name "AUTHOR") "CERN DEM MR")
      )
      (libsource (lib "Resistors") (part "Resistor - 1%"))
    )
    (comp (ref "R337")
      (value "120")
      (footprint "RESC1005X40N")
      (description "Resistor - 1%")
      (fields
        (field (name "PART NUMBER") "R0402_120R_1%_0.0625W_100PPM")
        (field (name "POWER") "0.0625W")
        (field (name "AUTHOR") "CERN DEM JLC")
      )
      (libsource (lib "Resistors") (part "Resistor - 1%"))
    )
    (comp (ref "R338")
      (value "140")
      (footprint "RESC0603X28N")
      (description "Resistor - 1%")
      (fields
        (field (name "PART NUMBER") "R0201_140R_1%_0.05W_200PPM")
        (field (name "POWER") "0.05W")
        (field (name "AUTHOR") "CERN DEM MR")
      )
      (libsource (lib "Resistors") (part "Resistor - 1%"))
    )
    (comp (ref "R339")
      (value "140")
      (footprint "RESC0603X28N")
      (description "Resistor - 1%")
      (fields
        (field (name "PART NUMBER") "R0201_140R_1%_0.05W_200PPM")
        (field (name "POWER") "0.05W")
        (field (name "AUTHOR") "CERN DEM MR")
      )
      (libsource (lib "Resistors") (part "Resistor - 1%"))
    )
    (comp (ref "R340")
      (value "120")
      (footprint "RESC1005X40N")
      (description "Resistor - 1%")
      (fields
        (field (name "PART NUMBER") "R0402_120R_1%_0.0625W_100PPM")
        (field (name "POWER") "0.0625W")
        (field (name "AUTHOR") "CERN DEM JLC")
      )
      (libsource (lib "Resistors") (part "Resistor - 1%"))
    )
    (comp (ref "R341")
      (value "140")
      (footprint "RESC0603X28N")
      (description "Resistor - 1%")
      (fields
        (field (name "PART NUMBER") "R0201_140R_1%_0.05W_200PPM")
        (field (name "POWER") "0.05W")
        (field (name "AUTHOR") "CERN DEM MR")
      )
      (libsource (lib "Resistors") (part "Resistor - 1%"))
    )
    (comp (ref "R342")
      (value "140")
      (footprint "RESC0603X28N")
      (description "Resistor - 1%")
      (fields
        (field (name "PART NUMBER") "R0201_140R_1%_0.05W_200PPM")
        (field (name "POWER") "0.05W")
        (field (name "AUTHOR") "CERN DEM MR")
      )
      (libsource (lib "Resistors") (part "Resistor - 1%"))
    )
    (comp (ref "R343")
      (value "120")
      (footprint "RESC1005X40N")
      (description "Resistor - 1%")
      (fields
        (field (name "PART NUMBER") "R0402_120R_1%_0.0625W_100PPM")
        (field (name "POWER") "0.0625W")
        (field (name "AUTHOR") "CERN DEM JLC")
      )
      (libsource (lib "Resistors") (part "Resistor - 1%"))
    )
    (comp (ref "R344")
      (value "140")
      (footprint "RESC0603X28N")
      (description "Resistor - 1%")
      (fields
        (field (name "PART NUMBER") "R0201_140R_1%_0.05W_200PPM")
        (field (name "POWER") "0.05W")
        (field (name "AUTHOR") "CERN DEM MR")
      )
      (libsource (lib "Resistors") (part "Resistor - 1%"))
    )
    (comp (ref "R345")
      (value "140")
      (footprint "RESC0603X28N")
      (description "Resistor - 1%")
      (fields
        (field (name "PART NUMBER") "R0201_140R_1%_0.05W_200PPM")
        (field (name "POWER") "0.05W")
        (field (name "AUTHOR") "CERN DEM MR")
      )
      (libsource (lib "Resistors") (part "Resistor - 1%"))
    )
    (comp (ref "R346")
      (value "120")
      (footprint "RESC1005X40N")
      (description "Resistor - 1%")
      (fields
        (field (name "PART NUMBER") "R0402_120R_1%_0.0625W_100PPM")
        (field (name "POWER") "0.0625W")
        (field (name "AUTHOR") "CERN DEM JLC")
      )
      (libsource (lib "Resistors") (part "Resistor - 1%"))
    )
    (comp (ref "R347")
      (value "140")
      (footprint "RESC0603X28N")
      (description "Resistor - 1%")
      (fields
        (field (name "PART NUMBER") "R0201_140R_1%_0.05W_200PPM")
        (field (name "POWER") "0.05W")
        (field (name "AUTHOR") "CERN DEM MR")
      )
      (libsource (lib "Resistors") (part "Resistor - 1%"))
    )
    (comp (ref "R348")
      (value "140")
      (footprint "RESC0603X28N")
      (description "Resistor - 1%")
      (fields
        (field (name "PART NUMBER") "R0201_140R_1%_0.05W_200PPM")
        (field (name "POWER") "0.05W")
        (field (name "AUTHOR") "CERN DEM MR")
      )
      (libsource (lib "Resistors") (part "Resistor - 1%"))
    )
    (comp (ref "R349")
      (value "120")
      (footprint "RESC1005X40N")
      (description "Resistor - 1%")
      (fields
        (field (name "PART NUMBER") "R0402_120R_1%_0.0625W_100PPM")
        (field (name "POWER") "0.0625W")
        (field (name "AUTHOR") "CERN DEM JLC")
      )
      (libsource (lib "Resistors") (part "Resistor - 1%"))
    )
    (comp (ref "R350")
      (value "140")
      (footprint "RESC0603X28N")
      (description "Resistor - 1%")
      (fields
        (field (name "PART NUMBER") "R0201_140R_1%_0.05W_200PPM")
        (field (name "POWER") "0.05W")
        (field (name "AUTHOR") "CERN DEM MR")
      )
      (libsource (lib "Resistors") (part "Resistor - 1%"))
    )
    (comp (ref "R354")
      (value "10k")
      (footprint "RESC1005X40N")
      (description "Resistor - 1%")
      (fields
        (field (name "PART NUMBER") "R0402_10K_1%_0.0625W_100PPM")
        (field (name "POWER") "0.0625W")
        (field (name "AUTHOR") "CERN DEM JLC")
      )
      (libsource (lib "Resistors") (part "Resistor - 1%"))
    )
    (comp (ref "R355")
      (value "10k")
      (footprint "RESC1005X40N")
      (description "Resistor - 1%")
      (fields
        (field (name "PART NUMBER") "R0402_10K_1%_0.0625W_100PPM")
        (field (name "POWER") "0.0625W")
        (field (name "AUTHOR") "CERN DEM JLC")
      )
      (libsource (lib "Resistors") (part "Resistor - 1%"))
    )
    (comp (ref "T6")
      (value "BSS138LT1G")
      (footprint "SOT95P240X110-3N")
      (description "N-CHANNEL MOSFET WITH DIODE")
      (fields (field (name "MANUFACTURER") "ON SEMICONDUCTOR") (field (name "AUTHOR") "CERN DEM JLC"))
      (libsource (lib "ICs And Semiconductors") (part "N-MOSFET-D 1G 2S 3D"))
    )
    (comp (ref "T7")
      (value "BSS138LT1G")
      (footprint "SOT95P240X110-3N")
      (description "N-CHANNEL MOSFET WITH DIODE")
      (fields (field (name "MANUFACTURER") "ON SEMICONDUCTOR") (field (name "AUTHOR") "CERN DEM JLC"))
      (libsource (lib "ICs And Semiconductors") (part "N-MOSFET-D 1G 2S 3D"))
    )
    (comp (ref "T8")
      (value "BSS138LT1G")
      (footprint "SOT95P240X110-3N")
      (description "N-CHANNEL MOSFET WITH DIODE")
      (fields (field (name "MANUFACTURER") "ON SEMICONDUCTOR") (field (name "AUTHOR") "CERN DEM JLC"))
      (libsource (lib "ICs And Semiconductors") (part "N-MOSFET-D 1G 2S 3D"))
    )
    (comp (ref "T9")
      (value "BSS138LT1G")
      (footprint "SOT95P240X110-3N")
      (description "N-CHANNEL MOSFET WITH DIODE")
      (fields (field (name "MANUFACTURER") "ON SEMICONDUCTOR") (field (name "AUTHOR") "CERN DEM JLC"))
      (libsource (lib "ICs And Semiconductors") (part "N-MOSFET-D 1G 2S 3D"))
    )
    (comp (ref "T16")
      (value "BSS138LT1G")
      (footprint "SOT95P240X110-3N")
      (description "N-CHANNEL MOSFET WITH DIODE")
      (fields (field (name "MANUFACTURER") "ON SEMICONDUCTOR") (field (name "AUTHOR") "CERN DEM JLC"))
      (libsource (lib "") (part "N-MOSFET-D 1G 2S 3D_1"))
    )
    (comp (ref "TP12")
      (value "Test Point")
      (footprint "TPS127")
      (fields (field (name "PART NUMBER") "SMD_PAD_1.27X1.27MM") (field (name "AUTHOR") "CERN DEM JLC"))
      (libsource (lib "Eletro-mechanical") (part "Test Point"))
    )
    (comp (ref "TP27")
      (value "Test Point")
      (footprint "TPS127")
      (fields (field (name "PART NUMBER") "SMD_PAD_1.27X1.27MM") (field (name "AUTHOR") "CERN DEM JLC"))
      (libsource (lib "Eletro-mechanical") (part "Test Point"))
    )
    (comp (ref "TP28")
      (value "Test Point")
      (footprint "TPS127")
      (fields (field (name "PART NUMBER") "SMD_PAD_1.27X1.27MM") (field (name "AUTHOR") "CERN DEM JLC"))
      (libsource (lib "Eletro-mechanical") (part "Test Point"))
    )
    (comp (ref "TP29")
      (value "Test Point")
      (footprint "TPS127")
      (fields (field (name "PART NUMBER") "SMD_PAD_1.27X1.27MM") (field (name "AUTHOR") "CERN DEM JLC"))
      (libsource (lib "Eletro-mechanical") (part "Test Point"))
    )
    (comp (ref "TP31")
      (value "Test Point")
      (footprint "TPS127")
      (fields (field (name "PART NUMBER") "SMD_PAD_1.27X1.27MM") (field (name "AUTHOR") "CERN DEM JLC"))
      (libsource (lib "Eletro-mechanical") (part "Test Point"))
    )
    (comp (ref "U1")
      (value "ICE40HX8K-CT256")
      (footprint "LATC-caBGA-256")
      (fields (field (name "MANUFACTURER") "Lattice Semiconductor"))
      (libsource (lib "Altium Content Vault") (part "LATC-HX8K-caBGA-256"))
    )
  )
  (nets
    (net (code "3") (name "/BP_I2C.SCL") (class "Default")
      (node (ref "R233") (pin "1") (pinfunction "1_1") (pintype "passive"))
    )
    (net (code "4") (name "/BP_I2C.SDA") (class "Default")
      (node (ref "R3") (pin "1") (pinfunction "1_1") (pintype "passive"))
    )
    (net (code "5") (name "/BP_IO.LVDS_N0") (class "Default")
      (node (ref "R252") (pin "1") (pinfunction "1_1") (pintype "passive"))
    )
    (net (code "6") (name "/BP_IO.LVDS_N1") (class "Default")
      (node (ref "R253") (pin "1") (pinfunction "1_1") (pintype "passive"))
    )
    (net (code "7") (name "/BP_IO.LVDS_N2") (class "Default")
      (node (ref "R254") (pin "1") (pinfunction "1_1") (pintype "passive"))
    )
    (net (code "8") (name "/BP_IO.LVDS_N3") (class "Default")
      (node (ref "R255") (pin "1") (pinfunction "1_1") (pintype "passive"))
    )
    (net (code "9") (name "/BP_IO.LVDS_N4") (class "Default")
      (node (ref "R256") (pin "1") (pinfunction "1_1") (pintype "passive"))
    )
    (net (code "10") (name "/BP_IO.LVDS_N5") (class "Default")
      (node (ref "R257") (pin "1") (pinfunction "1_1") (pintype "passive"))
    )
    (net (code "11") (name "/BP_IO.LVDS_N6") (class "Default")
      (node (ref "R258") (pin "1") (pinfunction "1_1") (pintype "passive"))
    )
    (net (code "12") (name "/BP_IO.LVDS_N7") (class "Default")
      (node (ref "R259") (pin "1") (pinfunction "1_1") (pintype "passive"))
    )
    (net (code "13") (name "/BP_IO.LVDS_N8") (class "Default")
      (node (ref "R260") (pin "1") (pinfunction "1_1") (pintype "passive"))
    )
    (net (code "14") (name "/BP_IO.LVDS_N9") (class "Default")
      (node (ref "R261") (pin "1") (pinfunction "1_1") (pintype "passive"))
    )
    (net (code "15") (name "/BP_IO.LVDS_N10") (class "Default")
      (node (ref "R262") (pin "1") (pinfunction "1_1") (pintype "passive"))
    )
    (net (code "16") (name "/BP_IO.LVDS_N11") (class "Default")
      (node (ref "R263") (pin "1") (pinfunction "1_1") (pintype "passive"))
    )
    (net (code "17") (name "/BP_IO.LVDS_N12") (class "Default")
      (node (ref "R264") (pin "1") (pinfunction "1_1") (pintype "passive"))
    )
    (net (code "18") (name "/BP_IO.LVDS_N13") (class "Default")
      (node (ref "R265") (pin "1") (pinfunction "1_1") (pintype "passive"))
    )
    (net (code "19") (name "/BP_IO.LVDS_N14") (class "Default")
      (node (ref "R266") (pin "1") (pinfunction "1_1") (pintype "passive"))
    )
    (net (code "20") (name "/BP_IO.LVDS_N15") (class "Default")
      (node (ref "R267") (pin "1") (pinfunction "1_1") (pintype "passive"))
    )
    (net (code "21") (name "/BP_IO.LVDS_P0") (class "Default")
      (node (ref "R235") (pin "1") (pinfunction "1_1") (pintype "passive"))
    )
    (net (code "22") (name "/BP_IO.LVDS_P1") (class "Default")
      (node (ref "R236") (pin "1") (pinfunction "1_1") (pintype "passive"))
    )
    (net (code "23") (name "/BP_IO.LVDS_P2") (class "Default")
      (node (ref "R238") (pin "1") (pinfunction "1_1") (pintype "passive"))
    )
    (net (code "24") (name "/BP_IO.LVDS_P3") (class "Default")
      (node (ref "R239") (pin "1") (pinfunction "1_1") (pintype "passive"))
    )
    (net (code "25") (name "/BP_IO.LVDS_P4") (class "Default")
      (node (ref "R240") (pin "1") (pinfunction "1_1") (pintype "passive"))
    )
    (net (code "26") (name "/BP_IO.LVDS_P5") (class "Default")
      (node (ref "R241") (pin "1") (pinfunction "1_1") (pintype "passive"))
    )
    (net (code "27") (name "/BP_IO.LVDS_P6") (class "Default")
      (node (ref "R242") (pin "1") (pinfunction "1_1") (pintype "passive"))
    )
    (net (code "28") (name "/BP_IO.LVDS_P7") (class "Default")
      (node (ref "R243") (pin "1") (pinfunction "1_1") (pintype "passive"))
    )
    (net (code "29") (name "/BP_IO.LVDS_P8") (class "Default")
      (node (ref "R244") (pin "1") (pinfunction "1_1") (pintype "passive"))
    )
    (net (code "30") (name "/BP_IO.LVDS_P9") (class "Default")
      (node (ref "R245") (pin "1") (pinfunction "1_1") (pintype "passive"))
    )
    (net (code "31") (name "/BP_IO.LVDS_P10") (class "Default")
      (node (ref "R246") (pin "1") (pinfunction "1_1") (pintype "passive"))
    )
    (net (code "32") (name "/BP_IO.LVDS_P11") (class "Default")
      (node (ref "R247") (pin "1") (pinfunction "1_1") (pintype "passive"))
    )
    (net (code "33") (name "/BP_IO.LVDS_P12") (class "Default")
      (node (ref "R248") (pin "1") (pinfunction "1_1") (pintype "passive"))
    )
    (net (code "34") (name "/BP_IO.LVDS_P13") (class "Default")
      (node (ref "R249") (pin "1") (pinfunction "1_1") (pintype "passive"))
    )
    (net (code "35") (name "/BP_IO.LVDS_P14") (class "Default")
      (node (ref "R250") (pin "1") (pinfunction "1_1") (pintype "passive"))
    )
    (net (code "36") (name "/BP_IO.LVDS_P15") (class "Default")
      (node (ref "R251") (pin "1") (pinfunction "1_1") (pintype "passive"))
    )
    (net (code "38") (name "/EEM0_0_N") (class "Default")
      (node (ref "J12") (pin "3") (pinfunction "3_3") (pintype "bidirectional"))
      (node (ref "R252") (pin "2") (pinfunction "2_2") (pintype "passive"))
      (node (ref "R333") (pin "2") (pinfunction "2_2") (pintype "passive"))
      (node (ref "R334") (pin "1") (pinfunction "1_1") (pintype "passive"))
    )
    (net (code "39") (name "/EEM0_0_P") (class "Default")
      (node (ref "J12") (pin "2") (pinfunction "2_2") (pintype "bidirectional"))
      (node (ref "R235") (pin "2") (pinfunction "2_2") (pintype "passive"))
      (node (ref "R334") (pin "2") (pinfunction "2_2") (pintype "passive"))
      (node (ref "R335") (pin "2") (pinfunction "2_2") (pintype "passive"))
    )
    (net (code "40") (name "/EEM0_1_N") (class "Default")
      (node (ref "J12") (pin "6") (pinfunction "6_6") (pintype "bidirectional"))
      (node (ref "R253") (pin "2") (pinfunction "2_2") (pintype "passive"))
      (node (ref "R83") (pin "1") (pinfunction "1_1") (pintype "passive"))
      (node (ref "R85") (pin "2") (pinfunction "2_2") (pintype "passive"))
    )
    (net (code "41") (name "/EEM0_1_P") (class "Default")
      (node (ref "J12") (pin "5") (pinfunction "5_5") (pintype "bidirectional"))
      (node (ref "R199") (pin "2") (pinfunction "2_2") (pintype "passive"))
      (node (ref "R236") (pin "2") (pinfunction "2_2") (pintype "passive"))
      (node (ref "R83") (pin "2") (pinfunction "2_2") (pintype "passive"))
    )
    (net (code "42") (name "/EEM0_2_N") (class "Default")
      (node (ref "J12") (pin "9") (pinfunction "9_9") (pintype "bidirectional"))
      (node (ref "R200") (pin "2") (pinfunction "2_2") (pintype "passive"))
      (node (ref "R203") (pin "1") (pinfunction "1_1") (pintype "passive"))
      (node (ref "R254") (pin "2") (pinfunction "2_2") (pintype "passive"))
    )
    (net (code "43") (name "/EEM0_2_P") (class "Default")
      (node (ref "J12") (pin "8") (pinfunction "8_8") (pintype "bidirectional"))
      (node (ref "R203") (pin "2") (pinfunction "2_2") (pintype "passive"))
      (node (ref "R206") (pin "2") (pinfunction "2_2") (pintype "passive"))
      (node (ref "R238") (pin "2") (pinfunction "2_2") (pintype "passive"))
    )
    (net (code "44") (name "/EEM0_3_N") (class "Default")
      (node (ref "J12") (pin "12") (pinfunction "12_12") (pintype "bidirectional"))
      (node (ref "R207") (pin "2") (pinfunction "2_2") (pintype "passive"))
      (node (ref "R208") (pin "1") (pinfunction "1_1") (pintype "passive"))
      (node (ref "R255") (pin "2") (pinfunction "2_2") (pintype "passive"))
    )
    (net (code "45") (name "/EEM0_3_P") (class "Default")
      (node (ref "J12") (pin "11") (pinfunction "11_11") (pintype "bidirectional"))
      (node (ref "R208") (pin "2") (pinfunction "2_2") (pintype "passive"))
      (node (ref "R209") (pin "2") (pinfunction "2_2") (pintype "passive"))
      (node (ref "R239") (pin "2") (pinfunction "2_2") (pintype "passive"))
    )
    (net (code "46") (name "/EEM0_4_N") (class "Default")
      (node (ref "J12") (pin "15") (pinfunction "15_15") (pintype "bidirectional"))
      (node (ref "R256") (pin "2") (pinfunction "2_2") (pintype "passive"))
      (node (ref "R348") (pin "2") (pinfunction "2_2") (pintype "passive"))
      (node (ref "R349") (pin "1") (pinfunction "1_1") (pintype "passive"))
    )
    (net (code "47") (name "/EEM0_4_P") (class "Default")
      (node (ref "J12") (pin "14") (pinfunction "14_14") (pintype "bidirectional"))
      (node (ref "R240") (pin "2") (pinfunction "2_2") (pintype "passive"))
      (node (ref "R349") (pin "2") (pinfunction "2_2") (pintype "passive"))
      (node (ref "R350") (pin "2") (pinfunction "2_2") (pintype "passive"))
    )
    (net (code "48") (name "/EEM0_5_N") (class "Default")
      (node (ref "J12") (pin "18") (pinfunction "18_18") (pintype "bidirectional"))
      (node (ref "R213") (pin "2") (pinfunction "2_2") (pintype "passive"))
      (node (ref "R214") (pin "1") (pinfunction "1_1") (pintype "passive"))
      (node (ref "R257") (pin "2") (pinfunction "2_2") (pintype "passive"))
    )
    (net (code "49") (name "/EEM0_5_P") (class "Default")
      (node (ref "J12") (pin "17") (pinfunction "17_17") (pintype "bidirectional"))
      (node (ref "R214") (pin "2") (pinfunction "2_2") (pintype "passive"))
      (node (ref "R215") (pin "2") (pinfunction "2_2") (pintype "passive"))
      (node (ref "R241") (pin "2") (pinfunction "2_2") (pintype "passive"))
    )
    (net (code "50") (name "/EEM0_6_N") (class "Default")
      (node (ref "J12") (pin "21") (pinfunction "21_21") (pintype "bidirectional"))
      (node (ref "R216") (pin "2") (pinfunction "2_2") (pintype "passive"))
      (node (ref "R217") (pin "1") (pinfunction "1_1") (pintype "passive"))
      (node (ref "R258") (pin "2") (pinfunction "2_2") (pintype "passive"))
    )
    (net (code "51") (name "/EEM0_6_P") (class "Default")
      (node (ref "J12") (pin "20") (pinfunction "20_20") (pintype "bidirectional"))
      (node (ref "R217") (pin "2") (pinfunction "2_2") (pintype "passive"))
      (node (ref "R242") (pin "2") (pinfunction "2_2") (pintype "passive"))
      (node (ref "R320") (pin "2") (pinfunction "2_2") (pintype "passive"))
    )
    (net (code "52") (name "/EEM0_7_N") (class "Default")
      (node (ref "J12") (pin "24") (pinfunction "24_24") (pintype "bidirectional"))
      (node (ref "R259") (pin "2") (pinfunction "2_2") (pintype "passive"))
      (node (ref "R321") (pin "2") (pinfunction "2_2") (pintype "passive"))
      (node (ref "R322") (pin "1") (pinfunction "1_1") (pintype "passive"))
    )
    (net (code "53") (name "/EEM0_7_P") (class "Default")
      (node (ref "J12") (pin "23") (pinfunction "23_23") (pintype "bidirectional"))
      (node (ref "R243") (pin "2") (pinfunction "2_2") (pintype "passive"))
      (node (ref "R322") (pin "2") (pinfunction "2_2") (pintype "passive"))
      (node (ref "R323") (pin "2") (pinfunction "2_2") (pintype "passive"))
    )
    (net (code "54") (name "/EEM1_0_N") (class "Default")
      (node (ref "J13") (pin "3") (pinfunction "3_3") (pintype "bidirectional"))
      (node (ref "R210") (pin "2") (pinfunction "2_2") (pintype "passive"))
      (node (ref "R211") (pin "1") (pinfunction "1_1") (pintype "passive"))
      (node (ref "R260") (pin "2") (pinfunction "2_2") (pintype "passive"))
    )
    (net (code "55") (name "/EEM1_0_P") (class "Default")
      (node (ref "J13") (pin "2") (pinfunction "2_2") (pintype "bidirectional"))
      (node (ref "R211") (pin "2") (pinfunction "2_2") (pintype "passive"))
      (node (ref "R212") (pin "2") (pinfunction "2_2") (pintype "passive"))
      (node (ref "R244") (pin "2") (pinfunction "2_2") (pintype "passive"))
    )
    (net (code "56") (name "/EEM1_1_N") (class "Default")
      (node (ref "J13") (pin "6") (pinfunction "6_6") (pintype "bidirectional"))
      (node (ref "R261") (pin "2") (pinfunction "2_2") (pintype "passive"))
      (node (ref "R324") (pin "2") (pinfunction "2_2") (pintype "passive"))
      (node (ref "R325") (pin "1") (pinfunction "1_1") (pintype "passive"))
    )
    (net (code "57") (name "/EEM1_1_P") (class "Default")
      (node (ref "J13") (pin "5") (pinfunction "5_5") (pintype "bidirectional"))
      (node (ref "R245") (pin "2") (pinfunction "2_2") (pintype "passive"))
      (node (ref "R325") (pin "2") (pinfunction "2_2") (pintype "passive"))
      (node (ref "R326") (pin "2") (pinfunction "2_2") (pintype "passive"))
    )
    (net (code "58") (name "/EEM1_2_N") (class "Default")
      (node (ref "J13") (pin "9") (pinfunction "9_9") (pintype "bidirectional"))
      (node (ref "R262") (pin "2") (pinfunction "2_2") (pintype "passive"))
      (node (ref "R327") (pin "2") (pinfunction "2_2") (pintype "passive"))
      (node (ref "R328") (pin "1") (pinfunction "1_1") (pintype "passive"))
    )
    (net (code "59") (name "/EEM1_2_P") (class "Default")
      (node (ref "J13") (pin "8") (pinfunction "8_8") (pintype "bidirectional"))
      (node (ref "R246") (pin "2") (pinfunction "2_2") (pintype "passive"))
      (node (ref "R328") (pin "2") (pinfunction "2_2") (pintype "passive"))
      (node (ref "R329") (pin "2") (pinfunction "2_2") (pintype "passive"))
    )
    (net (code "60") (name "/EEM1_3_N") (class "Default")
      (node (ref "J13") (pin "12") (pinfunction "12_12") (pintype "bidirectional"))
      (node (ref "R263") (pin "2") (pinfunction "2_2") (pintype "passive"))
      (node (ref "R330") (pin "2") (pinfunction "2_2") (pintype "passive"))
      (node (ref "R331") (pin "1") (pinfunction "1_1") (pintype "passive"))
    )
    (net (code "61") (name "/EEM1_3_P") (class "Default")
      (node (ref "J13") (pin "11") (pinfunction "11_11") (pintype "bidirectional"))
      (node (ref "R247") (pin "2") (pinfunction "2_2") (pintype "passive"))
      (node (ref "R331") (pin "2") (pinfunction "2_2") (pintype "passive"))
      (node (ref "R332") (pin "2") (pinfunction "2_2") (pintype "passive"))
    )
    (net (code "62") (name "/EEM1_4_N") (class "Default")
      (node (ref "J13") (pin "15") (pinfunction "15_15") (pintype "bidirectional"))
      (node (ref "R264") (pin "2") (pinfunction "2_2") (pintype "passive"))
      (node (ref "R336") (pin "2") (pinfunction "2_2") (pintype "passive"))
      (node (ref "R337") (pin "1") (pinfunction "1_1") (pintype "passive"))
    )
    (net (code "63") (name "/EEM1_4_P") (class "Default")
      (node (ref "J13") (pin "14") (pinfunction "14_14") (pintype "bidirectional"))
      (node (ref "R248") (pin "2") (pinfunction "2_2") (pintype "passive"))
      (node (ref "R337") (pin "2") (pinfunction "2_2") (pintype "passive"))
      (node (ref "R338") (pin "2") (pinfunction "2_2") (pintype "passive"))
    )
    (net (code "64") (name "/EEM1_5_N") (class "Default")
      (node (ref "J13") (pin "18") (pinfunction "18_18") (pintype "bidirectional"))
      (node (ref "R265") (pin "2") (pinfunction "2_2") (pintype "passive"))
      (node (ref "R339") (pin "2") (pinfunction "2_2") (pintype "passive"))
      (node (ref "R340") (pin "1") (pinfunction "1_1") (pintype "passive"))
    )
    (net (code "65") (name "/EEM1_5_P") (class "Default")
      (node (ref "J13") (pin "17") (pinfunction "17_17") (pintype "bidirectional"))
      (node (ref "R249") (pin "2") (pinfunction "2_2") (pintype "passive"))
      (node (ref "R340") (pin "2") (pinfunction "2_2") (pintype "passive"))
      (node (ref "R341") (pin "2") (pinfunction "2_2") (pintype "passive"))
    )
    (net (code "66") (name "/EEM1_6_N") (class "Default")
      (node (ref "J13") (pin "21") (pinfunction "21_21") (pintype "bidirectional"))
      (node (ref "R266") (pin "2") (pinfunction "2_2") (pintype "passive"))
      (node (ref "R342") (pin "2") (pinfunction "2_2") (pintype "passive"))
      (node (ref "R343") (pin "1") (pinfunction "1_1") (pintype "passive"))
    )
    (net (code "67") (name "/EEM1_6_P") (class "Default")
      (node (ref "J13") (pin "20") (pinfunction "20_20") (pintype "bidirectional"))
      (node (ref "R250") (pin "2") (pinfunction "2_2") (pintype "passive"))
      (node (ref "R343") (pin "2") (pinfunction "2_2") (pintype "passive"))
      (node (ref "R344") (pin "2") (pinfunction "2_2") (pintype "passive"))
    )
    (net (code "68") (name "/EEM1_7_N") (class "Default")
      (node (ref "J13") (pin "24") (pinfunction "24_24") (pintype "bidirectional"))
      (node (ref "R267") (pin "2") (pinfunction "2_2") (pintype "passive"))
      (node (ref "R345") (pin "2") (pinfunction "2_2") (pintype "passive"))
      (node (ref "R346") (pin "1") (pinfunction "1_1") (pintype "passive"))
    )
    (net (code "69") (name "/EEM1_7_P") (class "Default")
      (node (ref "J13") (pin "23") (pinfunction "23_23") (pintype "bidirectional"))
      (node (ref "R251") (pin "2") (pinfunction "2_2") (pintype "passive"))
      (node (ref "R346") (pin "2") (pinfunction "2_2") (pintype "passive"))
      (node (ref "R347") (pin "2") (pinfunction "2_2") (pintype "passive"))
    )
    (net (code "70") (name "/EEMR0_0_N") (class "Default")
      (node (ref "R333") (pin "1") (pinfunction "1_1") (pintype "passive"))
      (node (ref "U1") (pin "J5") (pinfunction "IOL_13A_J5") (pintype "bidirectional"))
    )
    (net (code "71") (name "/EEMR0_0_P") (class "Default")
      (node (ref "R335") (pin "1") (pinfunction "1_1") (pintype "passive"))
      (node (ref "U1") (pin "G1") (pinfunction "IOL_13B_GBIN7_G1") (pintype "bidirectional"))
    )
    (net (code "72") (name "/EEMR0_1_N") (class "Default")
      (node (ref "R85") (pin "1") (pinfunction "1_1") (pintype "passive"))
      (node (ref "U1") (pin "K4") (pinfunction "IOL_18A_K4") (pintype "bidirectional"))
    )
    (net (code "73") (name "/EEMR0_1_P") (class "Default")
      (node (ref "R199") (pin "1") (pinfunction "1_1") (pintype "passive"))
      (node (ref "U1") (pin "M1") (pinfunction "IOL_18B_M1") (pintype "bidirectional"))
    )
    (net (code "74") (name "/EEMR0_2_N") (class "Default")
      (node (ref "R200") (pin "1") (pinfunction "1_1") (pintype "passive"))
      (node (ref "U1") (pin "K1") (pinfunction "IOL_16A_K1") (pintype "bidirectional"))
    )
    (net (code "75") (name "/EEMR0_2_P") (class "Default")
      (node (ref "R206") (pin "1") (pinfunction "1_1") (pintype "passive"))
      (node (ref "U1") (pin "K3") (pinfunction "IOL_16B_K3") (pintype "bidirectional"))
    )
    (net (code "76") (name "/EEMR0_3_N") (class "Default")
      (node (ref "R207") (pin "1") (pinfunction "1_1") (pintype "passive"))
      (node (ref "U1") (pin "J4") (pinfunction "IOL_12A_J4") (pintype "bidirectional"))
    )
    (net (code "77") (name "/EEMR0_3_P") (class "Default")
      (node (ref "R209") (pin "1") (pinfunction "1_1") (pintype "passive"))
      (node (ref "U1") (pin "H2") (pinfunction "IOL_12B_H2") (pintype "bidirectional"))
    )
    (net (code "78") (name "/EEMR0_4_N") (class "Default")
      (node (ref "R348") (pin "1") (pinfunction "1_1") (pintype "passive"))
      (node (ref "U1") (pin "H4") (pinfunction "IOL_11A_H4") (pintype "bidirectional"))
    )
    (net (code "79") (name "/EEMR0_4_P") (class "Default")
      (node (ref "R350") (pin "1") (pinfunction "1_1") (pintype "passive"))
      (node (ref "U1") (pin "G2") (pinfunction "IOL_11B_G2") (pintype "bidirectional"))
    )
    (net (code "80") (name "/EEMR0_5_N") (class "Default")
      (node (ref "R213") (pin "1") (pinfunction "1_1") (pintype "passive"))
      (node (ref "U1") (pin "G4") (pinfunction "IOL_6A_G4") (pintype "bidirectional"))
    )
    (net (code "81") (name "/EEMR0_5_P") (class "Default")
      (node (ref "R215") (pin "1") (pinfunction "1_1") (pintype "passive"))
      (node (ref "U1") (pin "E3") (pinfunction "IOL_6B_E3") (pintype "bidirectional"))
    )
    (net (code "82") (name "/EEMR0_6_N") (class "Default")
      (node (ref "R216") (pin "1") (pinfunction "1_1") (pintype "passive"))
      (node (ref "U1") (pin "F4") (pinfunction "IOL_4A_F4") (pintype "bidirectional"))
    )
    (net (code "83") (name "/EEMR0_6_P") (class "Default")
      (node (ref "R320") (pin "1") (pinfunction "1_1") (pintype "passive"))
      (node (ref "U1") (pin "D2") (pinfunction "IOL_4B_D2") (pintype "bidirectional"))
    )
    (net (code "84") (name "/EEMR0_7_N") (class "Default")
      (node (ref "R321") (pin "1") (pinfunction "1_1") (pintype "passive"))
      (node (ref "U1") (pin "E4") (pinfunction "IOL_1A_E4") (pintype "bidirectional"))
    )
    (net (code "85") (name "/EEMR0_7_P") (class "Default")
      (node (ref "R323") (pin "1") (pinfunction "1_1") (pintype "passive"))
      (node (ref "U1") (pin "B2") (pinfunction "IOL_1B_B2") (pintype "bidirectional"))
    )
    (net (code "86") (name "/EEMR1_0_N") (class "Default")
      (node (ref "R210") (pin "1") (pinfunction "1_1") (pintype "passive"))
      (node (ref "U1") (pin "J3") (pinfunction "IOL_14A_GBIN6_J3") (pintype "bidirectional"))
    )
    (net (code "87") (name "/EEMR1_0_P") (class "Default")
      (node (ref "R212") (pin "1") (pinfunction "1_1") (pintype "passive"))
      (node (ref "U1") (pin "H1") (pinfunction "IOL_14B_H1") (pintype "bidirectional"))
    )
    (net (code "88") (name "/EEMR1_1_N") (class "Default")
      (node (ref "R324") (pin "1") (pinfunction "1_1") (pintype "passive"))
      (node (ref "U1") (pin "L4") (pinfunction "IOL_17A_L4") (pintype "bidirectional"))
    )
    (net (code "89") (name "/EEMR1_1_P") (class "Default")
      (node (ref "R326") (pin "1") (pinfunction "1_1") (pintype "passive"))
      (node (ref "U1") (pin "L1") (pinfunction "IOL_17B_L1") (pintype "bidirectional"))
    )
    (net (code "90") (name "/EEMR1_2_N") (class "Default")
      (node (ref "R327") (pin "1") (pinfunction "1_1") (pintype "passive"))
      (node (ref "U1") (pin "J2") (pinfunction "IOL_15A_J2") (pintype "bidirectional"))
    )
    (net (code "91") (name "/EEMR1_2_P") (class "Default")
      (node (ref "R329") (pin "1") (pinfunction "1_1") (pintype "passive"))
      (node (ref "U1") (pin "J1") (pinfunction "IOL_15B_J1") (pintype "bidirectional"))
    )
    (net (code "92") (name "/EEMR1_3_N") (class "Default")
      (node (ref "R330") (pin "1") (pinfunction "1_1") (pintype "passive"))
      (node (ref "U1") (pin "H3") (pinfunction "IOL_9A_H3") (pintype "bidirectional"))
    )
    (net (code "93") (name "/EEMR1_3_P") (class "Default")
      (node (ref "R332") (pin "1") (pinfunction "1_1") (pintype "passive"))
      (node (ref "U1") (pin "F2") (pinfunction "IOL_9B_F2") (pintype "bidirectional"))
    )
    (net (code "94") (name "/EEMR1_4_N") (class "Default")
      (node (ref "R336") (pin "1") (pinfunction "1_1") (pintype "passive"))
      (node (ref "U1") (pin "H5") (pinfunction "IOL_7A_H5") (pintype "bidirectional"))
    )
    (net (code "95") (name "/EEMR1_4_P") (class "Default")
      (node (ref "R338") (pin "1") (pinfunction "1_1") (pintype "passive"))
      (node (ref "U1") (pin "E2") (pinfunction "IOL_7B_E2") (pintype "bidirectional"))
    )
    (net (code "96") (name "/EEMR1_5_N") (class "Default")
      (node (ref "R339") (pin "1") (pinfunction "1_1") (pintype "passive"))
      (node (ref "U1") (pin "G5") (pinfunction "IOL_5A_G5") (pintype "bidirectional"))
    )
    (net (code "97") (name "/EEMR1_5_P") (class "Default")
      (node (ref "R341") (pin "1") (pinfunction "1_1") (pintype "passive"))
      (node (ref "U1") (pin "D1") (pinfunction "IOL_5B_D1") (pintype "bidirectional"))
    )
    (net (code "98") (name "/EEMR1_6_N") (class "Default")
      (node (ref "R342") (pin "1") (pinfunction "1_1") (pintype "passive"))
      (node (ref "U1") (pin "C1") (pinfunction "IOL_3A_C1") (pintype "bidirectional"))
    )
    (net (code "99") (name "/EEMR1_6_P") (class "Default")
      (node (ref "R344") (pin "1") (pinfunction "1_1") (pintype "passive"))
      (node (ref "U1") (pin "C2") (pinfunction "IOL_3B_C2") (pintype "bidirectional"))
    )
    (net (code "100") (name "/EEMR1_7_N") (class "Default")
      (node (ref "R345") (pin "1") (pinfunction "1_1") (pintype "passive"))
      (node (ref "U1") (pin "F5") (pinfunction "IOL_2A_F5") (pintype "bidirectional"))
    )
    (net (code "101") (name "/EEMR1_7_P") (class "Default")
      (node (ref "R347") (pin "1") (pinfunction "1_1") (pintype "passive"))
      (node (ref "U1") (pin "B1") (pinfunction "IOL_2B_B1") (pintype "bidirectional"))
    )
    (net (code "102") (name "/I2C0_SCL") (class "Default")
      (node (ref "D1") (pin "3") (pinfunction "I/O2_3") (pintype "bidirectional"))
      (node (ref "IC31") (pin "1") (pinfunction "Y_1") (pintype "bidirectional"))
      (node (ref "IC32") (pin "1") (pinfunction "SCL_1") (pintype "input"))
      (node (ref "IC8") (pin "6") (pinfunction "SCL_6") (pintype "input"))
      (node (ref "J12") (pin "27") (pinfunction "27_27") (pintype "bidirectional"))
      (node (ref "R125") (pin "1") (pinfunction "1_1") (pintype "passive"))
      (node (ref "R354") (pin "1") (pinfunction "1_1") (pintype "passive"))
      (node (ref "T6") (pin "3") (pinfunction "D_3") (pintype "passive"))
      (node (ref "TP28") (pin "1") (pinfunction "1_1") (pintype "bidirectional"))
    )
    (net (code "103") (name "/I2C0_SDA") (class "Default")
      (node (ref "D1") (pin "2") (pinfunction "I/O1_2") (pintype "bidirectional"))
      (node (ref "IC31") (pin "4") (pinfunction "Y_4") (pintype "bidirectional"))
      (node (ref "IC32") (pin "3") (pinfunction "SDA_3") (pintype "bidirectional"))
      (node (ref "IC8") (pin "5") (pinfunction "SDA_5") (pintype "bidirectional"))
      (node (ref "J12") (pin "26") (pinfunction "26_26") (pintype "bidirectional"))
      (node (ref "R124") (pin "1") (pinfunction "1_1") (pintype "passive"))
      (node (ref "R355") (pin "1") (pinfunction "1_1") (pintype "passive"))
      (node (ref "T9") (pin "3") (pinfunction "D_3") (pintype "passive"))
      (node (ref "TP27") (pin "1") (pinfunction "1_1") (pintype "bidirectional"))
    )
    (net (code "104") (name "/I2C1_SCL") (class "Default")
      (node (ref "D2") (pin "3") (pinfunction "I/O2_3") (pintype "bidirectional"))
      (node (ref "IC14") (pin "6") (pinfunction "SCL_6") (pintype "input"))
      (node (ref "IC26") (pin "1") (pinfunction "SCL_1") (pintype "input"))
      (node (ref "J13") (pin "27") (pinfunction "27_27") (pintype "bidirectional"))
      (node (ref "R7") (pin "1") (pinfunction "1_1") (pintype "passive"))
      (node (ref "T7") (pin "3") (pinfunction "D_3") (pintype "passive"))
      (node (ref "TP12") (pin "1") (pinfunction "1_1") (pintype "bidirectional"))
    )
    (net (code "105") (name "/I2C1_SDA") (class "Default")
      (node (ref "D2") (pin "2") (pinfunction "I/O1_2") (pintype "bidirectional"))
      (node (ref "IC14") (pin "5") (pinfunction "SDA_5") (pintype "bidirectional"))
      (node (ref "IC26") (pin "3") (pinfunction "SDA_3") (pintype "bidirectional"))
      (node (ref "J13") (pin "26") (pinfunction "26_26") (pintype "bidirectional"))
      (node (ref "R9") (pin "1") (pinfunction "1_1") (pintype "passive"))
      (node (ref "T8") (pin "3") (pinfunction "D_3") (pintype "passive"))
      (node (ref "TP31") (pin "1") (pinfunction "1_1") (pintype "bidirectional"))
    )
    (net (code "106") (name "/LED_ERR") (class "Default")
      (node (ref "LD19") (pin "1") (pinfunction "C_1") (pintype "passive"))
      (node (ref "R11") (pin "1") (pinfunction "1_1") (pintype "passive"))
    )
    (net (code "107") (name "/LED_OVT") (class "Default")
      (node (ref "IC12") (pin "3") (pinfunction "O.S._3") (pintype "output"))
      (node (ref "LD7") (pin "3") (pinfunction "C_3") (pintype "passive"))
      (node (ref "R123") (pin "1") (pinfunction "1_1") (pintype "passive"))
    )
    (net (code "108") (name "/LED_RED") (class "Default")
      (node (ref "T16") (pin "1") (pinfunction "G_1") (pintype "passive"))
      (node (ref "U1") (pin "L7") (pinfunction "IOL_21A_L7") (pintype "bidirectional"))
    )
    (net (code "109") (name "/PWR_EN") (class "Default")
      (node (ref "R120") (pin "2") (pinfunction "2_2") (pintype "passive"))
      (node (ref "R123") (pin "2") (pinfunction "2_2") (pintype "passive"))
    )
    (net (code "110") (name "/SERVMOD_3V3") (class "Default")
      (node (ref "IC31") (pin "13") (pinfunction "E_13") (pintype "input"))
      (node (ref "IC31") (pin "5") (pinfunction "E_5") (pintype "input"))
    )
    (net (code "111") (name "/Switch_I2C.SCL") (class "Default")
      (node (ref "IC31") (pin "2") (pinfunction "Z_2") (pintype "bidirectional"))
      (node (ref "R233") (pin "2") (pinfunction "2_2") (pintype "passive"))
    )
    (net (code "112") (name "/Switch_I2C.SDA") (class "Default")
      (node (ref "IC31") (pin "3") (pinfunction "Z_3") (pintype "bidirectional"))
      (node (ref "R3") (pin "2") (pinfunction "2_2") (pintype "passive"))
    )
    (net (code "113") (name "/U1_F1") (class "Default")
      (node (ref "U1") (pin "F1") (pinfunction "IOL_10B_F1") (pintype "bidirectional"))
    )
    (net (code "114") (name "/U1_F3") (class "Default")
      (node (ref "U1") (pin "F3") (pinfunction "IOL_8B_F3") (pintype "bidirectional"))
    )
    (net (code "115") (name "/U1_G3") (class "Default")
      (node (ref "U1") (pin "G3") (pinfunction "IOL_8A_G3") (pintype "bidirectional"))
    )
    (net (code "116") (name "/U1_H6") (class "Default")
      (node (ref "U1") (pin "H6") (pinfunction "IOL_10A_H6") (pintype "bidirectional"))
    )
    (net (code "117") (name "/U1_K5") (class "Default")
      (node (ref "U1") (pin "K5") (pinfunction "IOL_20A_K5") (pintype "bidirectional"))
    )
    (net (code "118") (name "/U1_L3") (class "Default")
      (node (ref "U1") (pin "L3") (pinfunction "IOL_19B_L3") (pintype "bidirectional"))
    )
    (net (code "119") (name "/U1_L5") (class "Default")
      (node (ref "U1") (pin "L5") (pinfunction "IOL_23A_L5") (pintype "bidirectional"))
    )
    (net (code "120") (name "/U1_L6") (class "Default")
      (node (ref "U1") (pin "L6") (pinfunction "IOL_19A_L6") (pintype "bidirectional"))
    )
    (net (code "121") (name "/U1_M2") (class "Default")
      (node (ref "U1") (pin "M2") (pinfunction "IOL_20B_M2") (pintype "bidirectional"))
    )
    (net (code "122") (name "/U1_M3") (class "Default")
      (node (ref "U1") (pin "M3") (pinfunction "IOL_22B_M3") (pintype "bidirectional"))
    )
    (net (code "123") (name "/U1_M4") (class "Default")
      (node (ref "U1") (pin "M4") (pinfunction "IOL_24B_M4") (pintype "bidirectional"))
    )
    (net (code "124") (name "/U1_M5") (class "Default")
      (node (ref "U1") (pin "M5") (pinfunction "IOL_25B_M5") (pintype "bidirectional"))
    )
    (net (code "125") (name "/U1_M6") (class "Default")
      (node (ref "U1") (pin "M6") (pinfunction "IOL_22A_M6") (pintype "bidirectional"))
    )
    (net (code "126") (name "/U1_N2") (class "Default")
      (node (ref "U1") (pin "N2") (pinfunction "IOL_21B_N2") (pintype "bidirectional"))
    )
    (net (code "127") (name "/U1_N3") (class "Default")
      (node (ref "U1") (pin "N3") (pinfunction "IOL_23B_N3") (pintype "bidirectional"))
    )
    (net (code "128") (name "/U1_N4") (class "Default")
      (node (ref "U1") (pin "N4") (pinfunction "IOL_26B_N4") (pintype "bidirectional"))
    )
    (net (code "129") (name "/U1_P1") (class "Default")
      (node (ref "U1") (pin "P1") (pinfunction "IOL_24A_P1") (pintype "bidirectional"))
    )
    (net (code "130") (name "/U1_P2") (class "Default")
      (node (ref "U1") (pin "P2") (pinfunction "IOL_25A_P2") (pintype "bidirectional"))
    )
    (net (code "131") (name "/U1_R1") (class "Default")
      (node (ref "U1") (pin "R1") (pinfunction "IOL_26A_R1") (pintype "bidirectional"))
    )
    (net (code "134") (name "GND") (class "Default")
      (node (ref "C105") (pin "1") (pinfunction "1_1") (pintype "passive"))
      (node (ref "C2") (pin "1") (pinfunction "1_1") (pintype "passive"))
      (node (ref "C20") (pin "1") (pinfunction "1_1") (pintype "passive"))
      (node (ref "C38") (pin "1") (pinfunction "1_1") (pintype "passive"))
      (node (ref "D1") (pin "1") (pinfunction "GND_1") (pintype "power_in"))
      (node (ref "D2") (pin "1") (pinfunction "GND_1") (pintype "power_in"))
      (node (ref "IC12") (pin "4") (pinfunction "GND_4") (pintype "power_in"))
      (node (ref "IC14") (pin "4") (pinfunction "VSS_4") (pintype "power_in"))
      (node (ref "IC26") (pin "2") (pinfunction "VSS_2") (pintype "power_in"))
      (node (ref "IC31") (pin "10") (pinfunction "Z_10") (pintype "bidirectional"))
      (node (ref "IC31") (pin "11") (pinfunction "Y_11") (pintype "bidirectional"))
      (node (ref "IC31") (pin "12") (pinfunction "E_12") (pintype "input"))
      (node (ref "IC31") (pin "6") (pinfunction "E_6") (pintype "input"))
      (node (ref "IC31") (pin "7") (pinfunction "GND_7") (pintype "power_in"))
      (node (ref "IC31") (pin "8") (pinfunction "Y_8") (pintype "bidirectional"))
      (node (ref "IC31") (pin "9") (pinfunction "Z_9") (pintype "bidirectional"))
      (node (ref "IC32") (pin "2") (pinfunction "VSS_2") (pintype "power_in"))
      (node (ref "IC8") (pin "4") (pinfunction "VSS_4") (pintype "power_in"))
      (node (ref "J12") (pin "1") (pinfunction "1_1") (pintype "bidirectional"))
      (node (ref "J12") (pin "10") (pinfunction "10_10") (pintype "bidirectional"))
      (node (ref "J12") (pin "13") (pinfunction "13_13") (pintype "bidirectional"))
      (node (ref "J12") (pin "16") (pinfunction "16_16") (pintype "bidirectional"))
      (node (ref "J12") (pin "19") (pinfunction "19_19") (pintype "bidirectional"))
      (node (ref "J12") (pin "22") (pinfunction "22_22") (pintype "bidirectional"))
      (node (ref "J12") (pin "25") (pinfunction "25_25") (pintype "bidirectional"))
      (node (ref "J12") (pin "4") (pinfunction "4_4") (pintype "bidirectional"))
      (node (ref "J12") (pin "7") (pinfunction "7_7") (pintype "bidirectional"))
      (node (ref "J13") (pin "1") (pinfunction "1_1") (pintype "bidirectional"))
      (node (ref "J13") (pin "10") (pinfunction "10_10") (pintype "bidirectional"))
      (node (ref "J13") (pin "13") (pinfunction "13_13") (pintype "bidirectional"))
      (node (ref "J13") (pin "16") (pinfunction "16_16") (pintype "bidirectional"))
      (node (ref "J13") (pin "19") (pinfunction "19_19") (pintype "bidirectional"))
      (node (ref "J13") (pin "22") (pinfunction "22_22") (pintype "bidirectional"))
      (node (ref "J13") (pin "25") (pinfunction "25_25") (pintype "bidirectional"))
      (node (ref "J13") (pin "4") (pinfunction "4_4") (pintype "bidirectional"))
      (node (ref "J13") (pin "7") (pinfunction "7_7") (pintype "bidirectional"))
      (node (ref "R126") (pin "1") (pinfunction "1_1") (pintype "passive"))
      (node (ref "R127") (pin "1") (pinfunction "1_1") (pintype "passive"))
      (node (ref "R128") (pin "1") (pinfunction "1_1") (pintype "passive"))
      (node (ref "T16") (pin "2") (pinfunction "S_2") (pintype "passive"))
    )
    (net (code "135") (name "Net-(IC12-A0)") (class "Default")
      (node (ref "IC12") (pin "7") (pinfunction "A0_7") (pintype "input"))
      (node (ref "R128") (pin "2") (pinfunction "2_2") (pintype "passive"))
    )
    (net (code "136") (name "Net-(IC12-A1)") (class "Default")
      (node (ref "IC12") (pin "6") (pinfunction "A1_6") (pintype "input"))
      (node (ref "R127") (pin "2") (pinfunction "2_2") (pintype "passive"))
    )
    (net (code "137") (name "Net-(IC12-A2)") (class "Default")
      (node (ref "IC12") (pin "5") (pinfunction "A2_5") (pintype "input"))
      (node (ref "R126") (pin "2") (pinfunction "2_2") (pintype "passive"))
    )
    (net (code "138") (name "Net-(IC12-SCL)") (class "Default")
      (node (ref "IC12") (pin "2") (pinfunction "SCL_2") (pintype "input"))
      (node (ref "R122") (pin "1") (pinfunction "1_1") (pintype "passive"))
      (node (ref "R125") (pin "2") (pinfunction "2_2") (pintype "passive"))
    )
    (net (code "139") (name "Net-(IC12-SDA)") (class "Default")
      (node (ref "IC12") (pin "1") (pinfunction "SDA_1") (pintype "bidirectional"))
      (node (ref "R121") (pin "1") (pinfunction "1_1") (pintype "passive"))
      (node (ref "R124") (pin "2") (pinfunction "2_2") (pintype "passive"))
    )
    (net (code "140") (name "Net-(LD7B-A)") (class "Default")
      (node (ref "LD7") (pin "4") (pinfunction "A_4") (pintype "passive"))
      (node (ref "R143") (pin "2") (pinfunction "2_2") (pintype "passive"))
    )
    (net (code "141") (name "Net-(T6-G)") (class "Default")
      (node (ref "R13") (pin "1") (pinfunction "1_1") (pintype "passive"))
      (node (ref "T6") (pin "1") (pinfunction "G_1") (pintype "passive"))
    )
    (net (code "142") (name "Net-(T6-S)") (class "Default")
      (node (ref "R24") (pin "1") (pinfunction "1_1") (pintype "passive"))
      (node (ref "T6") (pin "2") (pinfunction "S_2") (pintype "passive"))
    )
    (net (code "143") (name "Net-(T7-G)") (class "Default")
      (node (ref "R53") (pin "1") (pinfunction "1_1") (pintype "passive"))
      (node (ref "T7") (pin "1") (pinfunction "G_1") (pintype "passive"))
    )
    (net (code "144") (name "Net-(T7-S)") (class "Default")
      (node (ref "R86") (pin "1") (pinfunction "1_1") (pintype "passive"))
      (node (ref "T7") (pin "2") (pinfunction "S_2") (pintype "passive"))
    )
    (net (code "145") (name "Net-(T8-G)") (class "Default")
      (node (ref "R66") (pin "1") (pinfunction "1_1") (pintype "passive"))
      (node (ref "T8") (pin "1") (pinfunction "G_1") (pintype "passive"))
    )
    (net (code "146") (name "Net-(T8-S)") (class "Default")
      (node (ref "R67") (pin "1") (pinfunction "1_1") (pintype "passive"))
      (node (ref "T8") (pin "2") (pinfunction "S_2") (pintype "passive"))
    )
    (net (code "147") (name "Net-(T9-G)") (class "Default")
      (node (ref "R16") (pin "1") (pinfunction "1_1") (pintype "passive"))
      (node (ref "T9") (pin "1") (pinfunction "G_1") (pintype "passive"))
    )
    (net (code "148") (name "Net-(T9-S)") (class "Default")
      (node (ref "R21") (pin "1") (pinfunction "1_1") (pintype "passive"))
      (node (ref "T9") (pin "2") (pinfunction "S_2") (pintype "passive"))
    )
    (net (code "149") (name "Net-(T16-D)") (class "Default")
      (node (ref "R11") (pin "2") (pinfunction "2_2") (pintype "passive"))
      (node (ref "T16") (pin "3") (pinfunction "D_3") (pintype "passive"))
    )
    (net (code "150") (name "P3V3") (class "Default")
      (node (ref "LD19") (pin "2") (pinfunction "A_2") (pintype "passive"))
      (node (ref "R13") (pin "2") (pinfunction "2_2") (pintype "passive"))
      (node (ref "R16") (pin "2") (pinfunction "2_2") (pintype "passive"))
      (node (ref "R21") (pin "2") (pinfunction "2_2") (pintype "passive"))
      (node (ref "R24") (pin "2") (pinfunction "2_2") (pintype "passive"))
      (node (ref "R53") (pin "2") (pinfunction "2_2") (pintype "passive"))
      (node (ref "R66") (pin "2") (pinfunction "2_2") (pintype "passive"))
      (node (ref "R67") (pin "2") (pinfunction "2_2") (pintype "passive"))
      (node (ref "R86") (pin "2") (pinfunction "2_2") (pintype "passive"))
    )
    (net (code "151") (name "P3V3_MP") (class "Default")
      (node (ref "C105") (pin "2") (pinfunction "2_2") (pintype "passive"))
      (node (ref "C2") (pin "2") (pinfunction "2_2") (pintype "passive"))
      (node (ref "C20") (pin "2") (pinfunction "2_2") (pintype "passive"))
      (node (ref "C38") (pin "2") (pinfunction "2_2") (pintype "passive"))
      (node (ref "D1") (pin "4") (pinfunction "VCC_4") (pintype "power_in"))
      (node (ref "D2") (pin "4") (pinfunction "VCC_4") (pintype "power_in"))
      (node (ref "IC12") (pin "8") (pinfunction "+VS_8") (pintype "power_in"))
      (node (ref "IC14") (pin "8") (pinfunction "VCC_8") (pintype "power_in"))
      (node (ref "IC26") (pin "4") (pinfunction "VCC_4") (pintype "power_in"))
      (node (ref "IC31") (pin "14") (pinfunction "VCC_14") (pintype "power_in"))
      (node (ref "IC32") (pin "4") (pinfunction "VCC_4") (pintype "power_in"))
      (node (ref "IC8") (pin "8") (pinfunction "VCC_8") (pintype "power_in"))
      (node (ref "J12") (pin "30") (pinfunction "30_30") (pintype "bidirectional"))
      (node (ref "J13") (pin "30") (pinfunction "30_30") (pintype "bidirectional"))
      (node (ref "R120") (pin "1") (pinfunction "1_1") (pintype "passive"))
      (node (ref "R121") (pin "2") (pinfunction "2_2") (pintype "passive"))
      (node (ref "R122") (pin "2") (pinfunction "2_2") (pintype "passive"))
      (node (ref "R143") (pin "1") (pinfunction "1_1") (pintype "passive"))
      (node (ref "R354") (pin "2") (pinfunction "2_2") (pintype "passive"))
      (node (ref "R355") (pin "2") (pinfunction "2_2") (pintype "passive"))
      (node (ref "R7") (pin "2") (pinfunction "2_2") (pintype "passive"))
      (node (ref "R9") (pin "2") (pinfunction "2_2") (pintype "passive"))
      (node (ref "TP29") (pin "1") (pinfunction "1_1") (pintype "bidirectional"))
    )
    (net (code "152") (name "P12V0") (class "Default")
      (node (ref "J12") (pin "28") (pinfunction "28_28") (pintype "bidirectional"))
      (node (ref "J12") (pin "29") (pinfunction "29_29") (pintype "bidirectional"))
      (node (ref "J13") (pin "28") (pinfunction "28_28") (pintype "bidirectional"))
      (node (ref "J13") (pin "29") (pinfunction "29_29") (pintype "bidirectional"))
      (node (ref "R268") (pin "2") (pinfunction "2_2") (pintype "passive"))
      (node (ref "R269") (pin "2") (pinfunction "2_2") (pintype "passive"))
      (node (ref "R270") (pin "2") (pinfunction "2_2") (pintype "passive"))
      (node (ref "R271") (pin "2") (pinfunction "2_2") (pintype "passive"))
    )
    (net (code "153") (name "P12V0_CPCIS") (class "Default")
      (node (ref "R268") (pin "1") (pinfunction "1_1") (pintype "passive"))
      (node (ref "R269") (pin "1") (pinfunction "1_1") (pintype "passive"))
      (node (ref "R270") (pin "1") (pinfunction "1_1") (pintype "passive"))
      (node (ref "R271") (pin "1") (pinfunction "1_1") (pintype "passive"))
    )
    (net (code "154") (name "unconnected-(IC8-A0_(NC)-Pad1)") (class "Default")
      (node (ref "IC8") (pin "1") (pinfunction "A0_(NC)_1") (pintype "input+no_connect"))
    )
    (net (code "155") (name "unconnected-(IC8-A1_(NC)-Pad2)") (class "Default")
      (node (ref "IC8") (pin "2") (pinfunction "A1_(NC)_2") (pintype "input+no_connect"))
    )
    (net (code "156") (name "unconnected-(IC8-A2_(NC)-Pad3)") (class "Default")
      (node (ref "IC8") (pin "3") (pinfunction "A2_(NC)_3") (pintype "input+no_connect"))
    )
    (net (code "157") (name "unconnected-(IC8-NC-Pad7)") (class "Default")
      (node (ref "IC8") (pin "7") (pinfunction "NC_7") (pintype "passive"))
    )
    (net (code "158") (name "unconnected-(IC14-A0_(NC)-Pad1)") (class "Default")
      (node (ref "IC14") (pin "1") (pinfunction "A0_(NC)_1") (pintype "input+no_connect"))
    )
    (net (code "159") (name "unconnected-(IC14-A1_(NC)-Pad2)") (class "Default")
      (node (ref "IC14") (pin "2") (pinfunction "A1_(NC)_2") (pintype "input+no_connect"))
    )
    (net (code "160") (name "unconnected-(IC14-A2_(NC)-Pad3)") (class "Default")
      (node (ref "IC14") (pin "3") (pinfunction "A2_(NC)_3") (pintype "input+no_connect"))
    )
    (net (code "161") (name "unconnected-(IC14-NC-Pad7)") (class "Default")
      (node (ref "IC14") (pin "7") (pinfunction "NC_7") (pintype "passive"))
    )
    (net (code "162") (name "unconnected-(IC26-NC-Pad5)") (class "Default")
      (node (ref "IC26") (pin "5") (pinfunction "NC_5") (pintype "passive"))
    )
    (net (code "163") (name "unconnected-(IC32-NC-Pad5)") (class "Default")
      (node (ref "IC32") (pin "5") (pinfunction "NC_5") (pintype "passive"))
    )
  )
)
